# PX4FMUv1_7.net
KiCad netlist of a schematic drawn in EAGLE
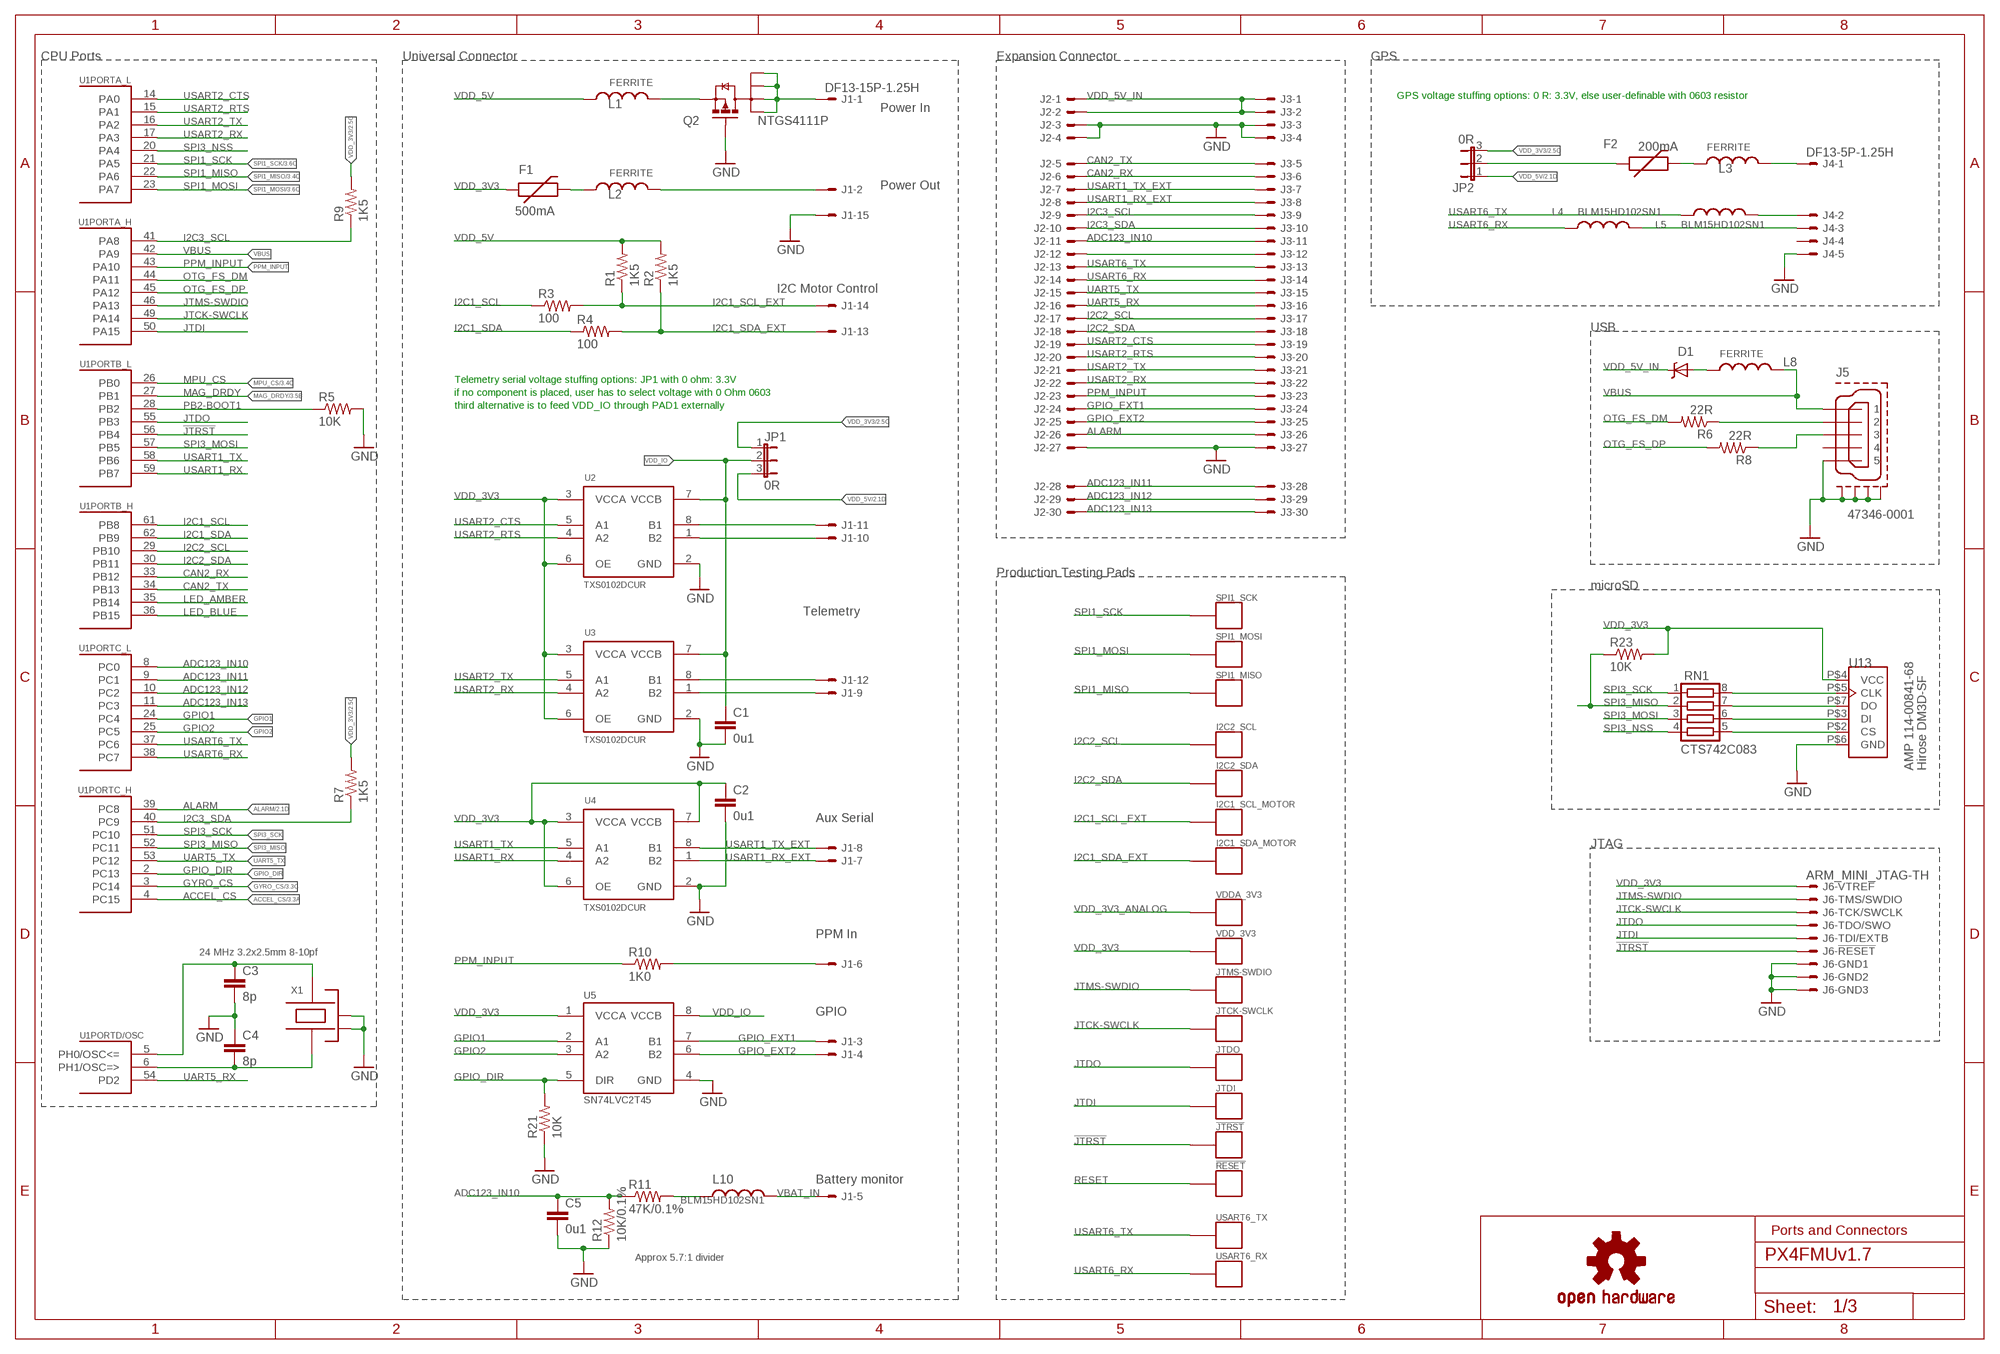
[diagram p0: schematic, sheet 1]
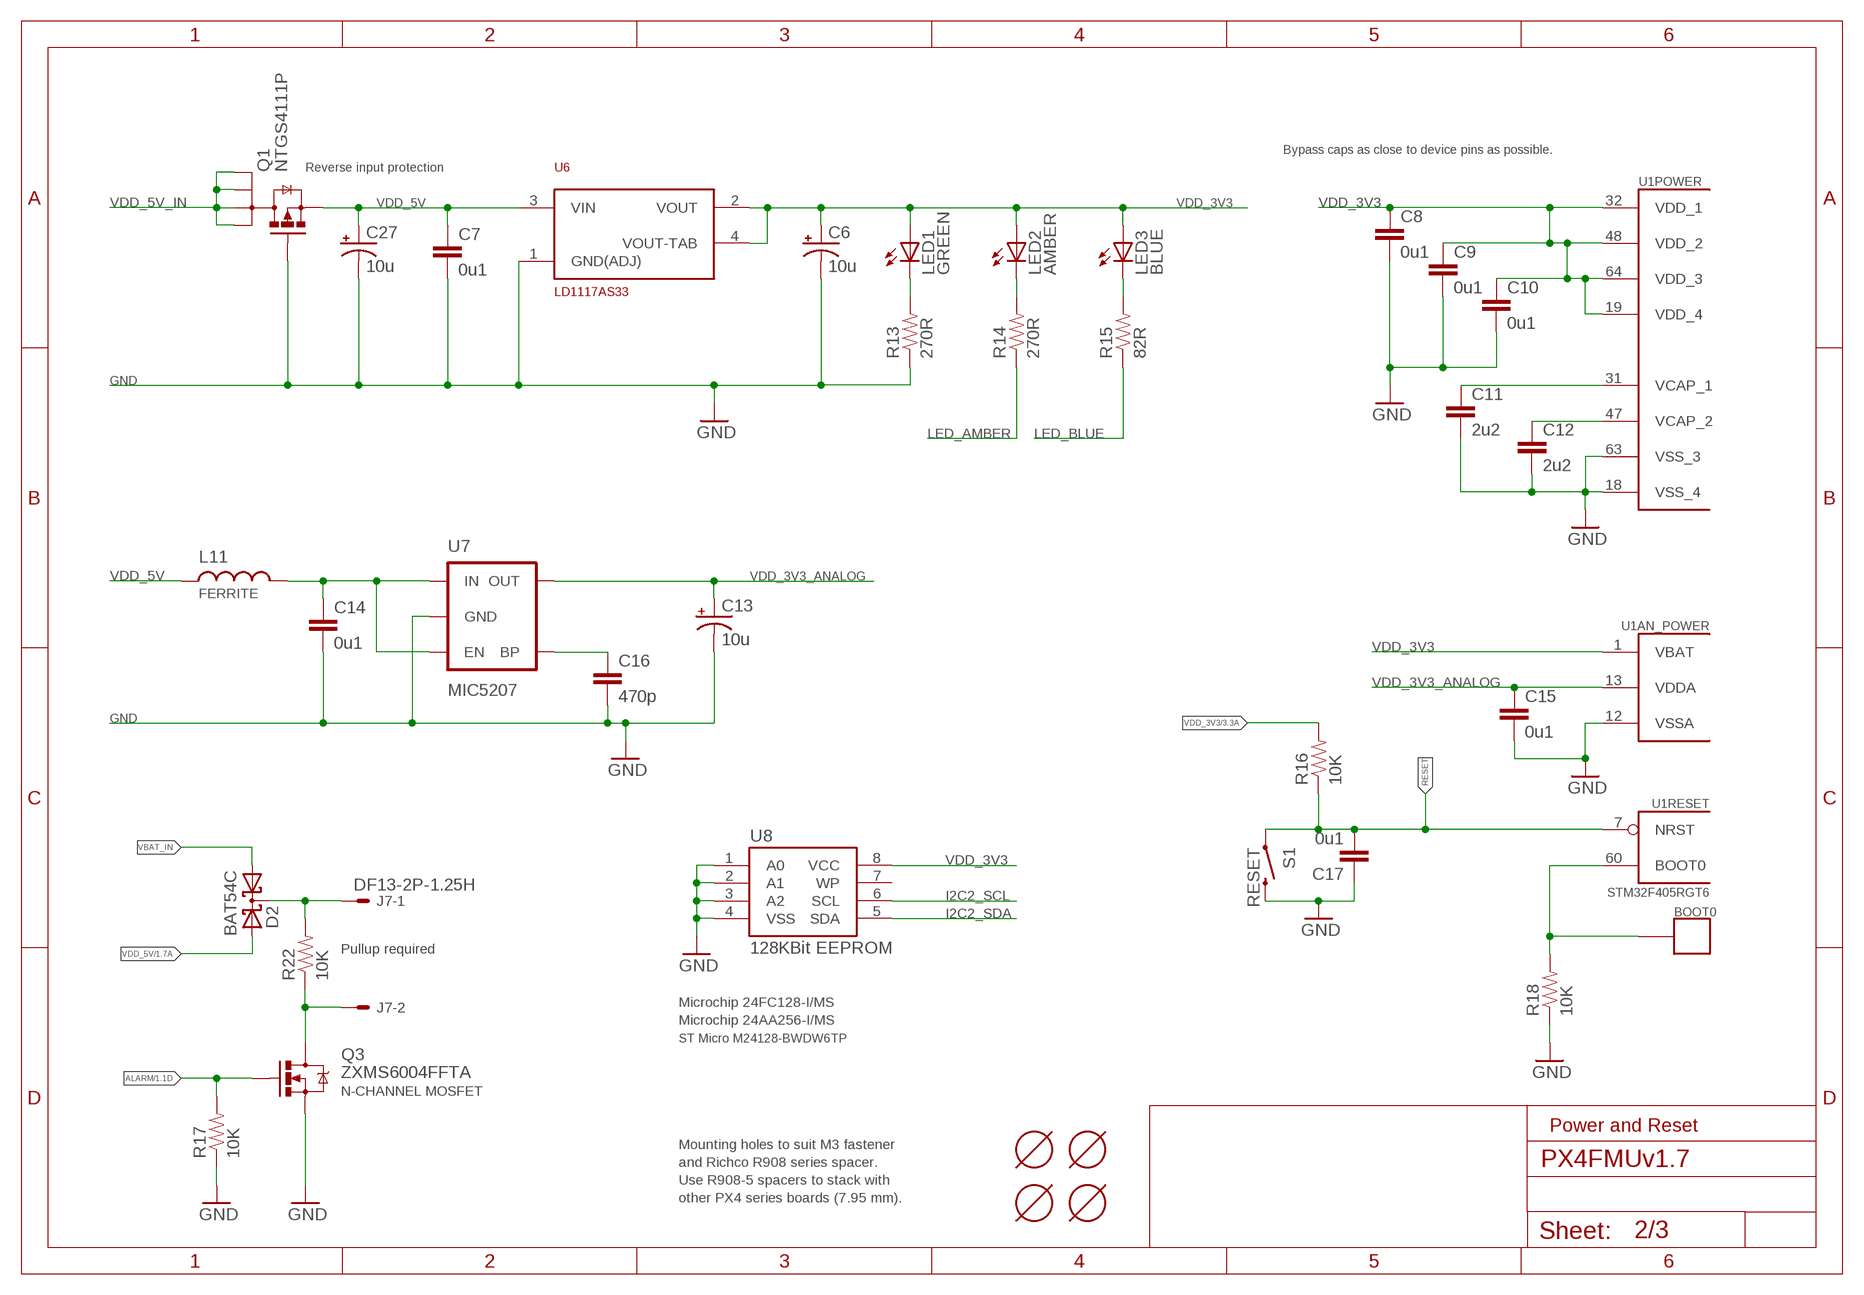
[diagram p1: schematic, sheet 2]
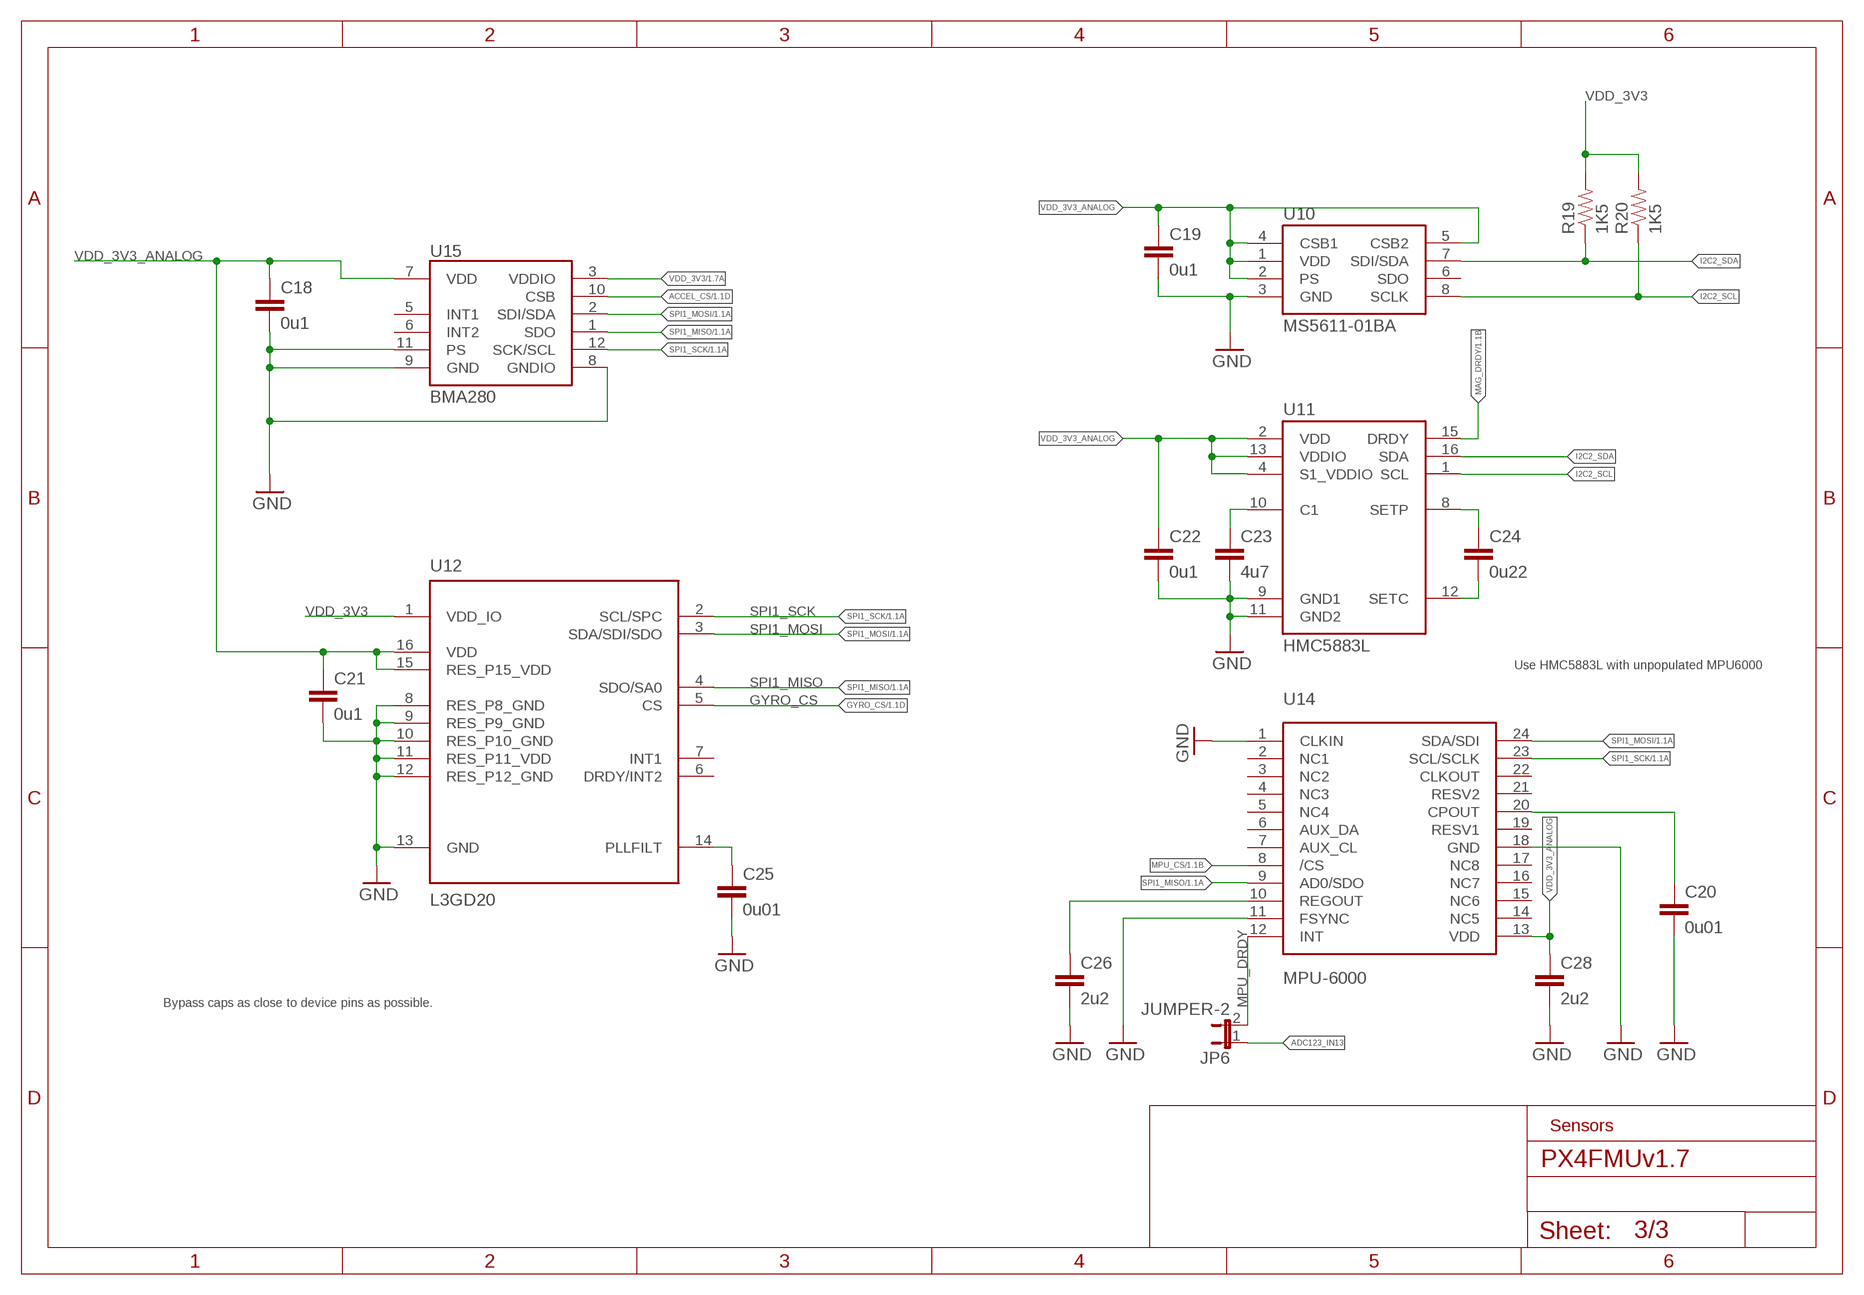
[diagram p2: schematic, sheet 3]

(export (version "E")
  (design (tool "Eeschema 10.0.6"))
  (components
    (comp (ref "C18")
      (value "0u1")
      (footprint "eagle-import:0402-CAP")
      (fields (field (name "PARTNO") "CC0402ZRY5V7BB104"))
      (libsource (lib "eagle-import") (part "CAP0402-CAP"))
    )
    (comp (ref "C19")
      (value "0u1")
      (footprint "eagle-import:0402-CAP")
      (fields (field (name "PARTNO") "CC0402ZRY5V7BB104"))
      (libsource (lib "eagle-import") (part "CAP0402-CAP"))
    )
    (comp (ref "C20")
      (value "0u01")
      (footprint "eagle-import:0402-CAP")
      (fields (field (name "PARTNO") "CC0402KRX7R7BB103"))
      (libsource (lib "eagle-import") (part "CAP0402-CAP"))
    )
    (comp (ref "C21")
      (value "0u1")
      (footprint "eagle-import:0402-CAP")
      (fields (field (name "PARTNO") "CC0402ZRY5V7BB104"))
      (libsource (lib "eagle-import") (part "CAP0402-CAP"))
    )
    (comp (ref "C22")
      (value "0u1")
      (footprint "eagle-import:0402-CAP")
      (fields (field (name "PARTNO") "CC0402ZRY5V7BB104"))
      (libsource (lib "eagle-import") (part "CAP0402-CAP"))
    )
    (comp (ref "C23")
      (value "4u7")
      (footprint "eagle-import:0402-CAP")
      (fields (field (name "PARTNO") "C1608Y5V0J475Z"))
      (libsource (lib "eagle-import") (part "CAP0402-CAP"))
    )
    (comp (ref "C24")
      (value "0u22")
      (footprint "eagle-import:0402-CAP")
      (fields (field (name "PARTNO") "C1005Y5V1C224Z"))
      (libsource (lib "eagle-import") (part "CAP0402-CAP"))
    )
    (comp (ref "C25")
      (value "0u01")
      (footprint "eagle-import:0402-CAP")
      (fields (field (name "PARTNO") "CC0402KRX7R7BB103"))
      (libsource (lib "eagle-import") (part "CAP0402-CAP"))
    )
    (comp (ref "C26")
      (value "2u2")
      (footprint "eagle-import:0402-CAP")
      (fields (field (name "PARTNO") "C1608Y5V1C225Z"))
      (libsource (lib "eagle-import") (part "CAP0402-CAP"))
    )
    (comp (ref "C28")
      (value "2u2")
      (footprint "eagle-import:0402-CAP")
      (fields (field (name "PARTNO") "C1608Y5V1C225Z"))
      (libsource (lib "eagle-import") (part "CAP0402-CAP"))
    )
    (comp (ref "JP6")
      (value "JUMPER-2")
      (footprint "eagle-import:SJ_2")
      (libsource (lib "eagle-import") (part "JUMPER-2"))
    )
    (comp (ref "R19")
      (value "1K5")
      (footprint "eagle-import:0402-RES")
      (fields (field (name "PARTNO") "RMCF0402JT1K50"))
      (libsource (lib "eagle-import") (part "RESISTOR0402-RES"))
    )
    (comp (ref "R20")
      (value "1K5")
      (footprint "eagle-import:0402-RES")
      (fields (field (name "PARTNO") "RMCF0402JT1K50"))
      (libsource (lib "eagle-import") (part "RESISTOR0402-RES"))
    )
    (comp (ref "U10")
      (value "MS5611-01BA")
      (footprint "eagle-import:MS5611-01BA")
      (libsource (lib "eagle-import") (part "MS5611-01BA"))
    )
    (comp (ref "U11")
      (value "HMC5883L")
      (footprint "eagle-import:HMC5883L-MAN")
      (libsource (lib "eagle-import") (part "HMC5883L"))
    )
    (comp (ref "U12")
      (value "L3GD20")
      (footprint "eagle-import:L3G4200DH-MAN")
      (libsource (lib "eagle-import") (part "L3G4200DH-LL"))
    )
    (comp (ref "U14")
      (value "MPU-6000")
      (footprint "eagle-import:QFN-24")
      (libsource (lib "eagle-import") (part "MPU-6000"))
    )
    (comp (ref "U15")
      (value "BMA280")
      (footprint "eagle-import:BMA280")
      (libsource (lib "eagle-import") (part "BMA280"))
    )
    (comp (ref "!JTRST")
      (value "PAD.04")
      (footprint "eagle-import:PAD.04X.04")
      (libsource (lib "eagle-import") (part "PAD.04"))
    )
    (comp (ref "!RESET")
      (value "PAD.04")
      (footprint "eagle-import:PAD.04X.04")
      (libsource (lib "eagle-import") (part "PAD.04"))
    )
    (comp (ref "C1")
      (value "0u1")
      (footprint "eagle-import:0402-CAP")
      (fields (field (name "PARTNO") "CC0402ZRY5V7BB104"))
      (libsource (lib "eagle-import") (part "CAP0402-CAP"))
    )
    (comp (ref "C2")
      (value "0u1")
      (footprint "eagle-import:0402-CAP")
      (fields (field (name "PARTNO") "CC0402ZRY5V7BB104"))
      (libsource (lib "eagle-import") (part "CAP0402-CAP"))
    )
    (comp (ref "C3")
      (value "8p")
      (footprint "eagle-import:0402-CAP")
      (fields (field (name "PARTNO") "C1005C0G1H080C"))
      (libsource (lib "eagle-import") (part "CAP0402-CAP"))
    )
    (comp (ref "C4")
      (value "8p")
      (footprint "eagle-import:0402-CAP")
      (fields (field (name "PARTNO") "C1005C0G1H080C"))
      (libsource (lib "eagle-import") (part "CAP0402-CAP"))
    )
    (comp (ref "C5")
      (value "0u1")
      (footprint "eagle-import:0402-CAP")
      (fields (field (name "PARTNO") "CC0402ZRY5V7BB104"))
      (libsource (lib "eagle-import") (part "CAP0402-CAP"))
    )
    (comp (ref "D1")
      (value "MSS1P4-M3")
      (footprint "eagle-import:MICROSMP")
      (fields (field (name "PARTNO") "MSS1P4-M3/89A"))
      (libsource (lib "eagle-import") (part "DIODE-SCHOTTKY_MSMP"))
    )
    (comp (ref "F1")
      (value "500mA")
      (footprint "eagle-import:0402-PTC")
      (fields (field (name "PARTNO") "MF-FSMF050X-2"))
      (libsource (lib "eagle-import") (part "PTC0402"))
    )
    (comp (ref "F2")
      (value "200mA")
      (footprint "eagle-import:0402-PTC")
      (fields (field (name "PARTNO") "MF-FSMF020X-2"))
      (libsource (lib "eagle-import") (part "PTC0402"))
    )
    (comp (ref "I2C1_SCL_MOTOR")
      (value "PAD.03")
      (footprint "eagle-import:PAD.03X.03")
      (libsource (lib "eagle-import") (part "PAD.03"))
    )
    (comp (ref "I2C1_SDA_MOTOR")
      (value "PAD.03")
      (footprint "eagle-import:PAD.03X.03")
      (libsource (lib "eagle-import") (part "PAD.03"))
    )
    (comp (ref "I2C2_SCL")
      (value "PAD.03")
      (footprint "eagle-import:PAD.03X.03")
      (libsource (lib "eagle-import") (part "PAD.03"))
    )
    (comp (ref "I2C2_SDA")
      (value "PAD.04")
      (footprint "eagle-import:PAD.04X.04")
      (libsource (lib "eagle-import") (part "PAD.04"))
    )
    (comp (ref "J1")
      (value "DF13-15P-1.25H")
      (footprint "eagle-import:DF13A-15P-1.25H")
      (fields (field (name "PARTNO") "DF13A-15P-1.25H(20)"))
      (libsource (lib "eagle-import") (part "DF13-15P-1.25?H"))
    )
    (comp (ref "J2")
      (value "HEADER_2X15-REV")
      (footprint "eagle-import:HEADER_2MM_2X15_REVERSE")
      (fields (field (name "BOM") "EXCLUDE") (field (name "PARTNO") "953230-2000-AR-PR"))
      (libsource (lib "eagle-import") (part "HEADER_2X15-REV"))
    )
    (comp (ref "J3")
      (value "HEADER_2X15")
      (footprint "eagle-import:HEADER_2MM_2X15")
      (fields (field (name "PARTNO") "953230-2000-AR-PR"))
      (libsource (lib "eagle-import") (part "HEADER_2X15-SMD"))
    )
    (comp (ref "J4")
      (value "DF13-5P-1.25H")
      (footprint "eagle-import:DF13A-5P-1.25H")
      (fields (field (name "PARTNO") "DF13A-5P-1.25H(20)"))
      (libsource (lib "eagle-import") (part "DF13-5P-1.25?H"))
    )
    (comp (ref "J5")
      (value "47346-0001")
      (footprint "eagle-import:MOLEX-47346-0001")
      (libsource (lib "eagle-import") (part "MOLEX-47346-0001"))
    )
    (comp (ref "J6")
      (value "ARM_MINI_JTAG-TH")
      (footprint "eagle-import:FTSH-105-01-XXX-DV")
      (fields (field (name "PARTNO") "M50-3900542"))
      (libsource (lib "eagle-import") (part "ARM_MINI_JTAG-TH"))
    )
    (comp (ref "JP1")
      (value "0R")
      (footprint "eagle-import:SJ_3_0603_PASTE1&2")
      (fields (field (name "PARTNO") "RMCF0402ZT0R00"))
      (libsource (lib "eagle-import") (part "JUMPER-30603"))
    )
    (comp (ref "JP2")
      (value "0R")
      (footprint "eagle-import:SJ_3_0603_PASTE1&2")
      (fields (field (name "PARTNO") "RMCF0402ZT0R00"))
      (libsource (lib "eagle-import") (part "JUMPER-30603"))
    )
    (comp (ref "JTCK-SWCLK")
      (value "PAD.04")
      (footprint "eagle-import:PAD.04X.04")
      (libsource (lib "eagle-import") (part "PAD.04"))
    )
    (comp (ref "JTDI")
      (value "PAD.04")
      (footprint "eagle-import:PAD.04X.04")
      (libsource (lib "eagle-import") (part "PAD.04"))
    )
    (comp (ref "JTDO")
      (value "PAD.04")
      (footprint "eagle-import:PAD.04X.04")
      (libsource (lib "eagle-import") (part "PAD.04"))
    )
    (comp (ref "JTMS-SWDIO")
      (value "PAD.04")
      (footprint "eagle-import:PAD.04X.04")
      (libsource (lib "eagle-import") (part "PAD.04"))
    )
    (comp (ref "L1")
      (value "FERRITE")
      (footprint "eagle-import:0402-IND")
      (fields (field (name "PARTNO") "BKP1005HS121-T"))
      (libsource (lib "eagle-import") (part "INDUCTOR0402"))
    )
    (comp (ref "L2")
      (value "FERRITE")
      (footprint "eagle-import:0402-IND")
      (fields (field (name "PARTNO") "BKP1005HS121-T"))
      (libsource (lib "eagle-import") (part "INDUCTOR0402"))
    )
    (comp (ref "L3")
      (value "FERRITE")
      (footprint "eagle-import:0402-IND")
      (fields (field (name "PARTNO") "BKP1005HS121-T"))
      (libsource (lib "eagle-import") (part "INDUCTOR0402"))
    )
    (comp (ref "L4")
      (value "BLM15HD102SN1")
      (footprint "eagle-import:0402-IND")
      (libsource (lib "eagle-import") (part "INDUCTOR0402"))
    )
    (comp (ref "L5")
      (value "BLM15HD102SN1")
      (footprint "eagle-import:0402-IND")
      (libsource (lib "eagle-import") (part "INDUCTOR0402"))
    )
    (comp (ref "L8")
      (value "FERRITE")
      (footprint "eagle-import:0402-IND")
      (fields (field (name "PARTNO") "BKP1005HS121-T"))
      (libsource (lib "eagle-import") (part "INDUCTOR0402"))
    )
    (comp (ref "L10")
      (value "BLM15HD102SN1")
      (footprint "eagle-import:0402-IND")
      (libsource (lib "eagle-import") (part "INDUCTOR0402"))
    )
    (comp (ref "Q2")
      (value "NTGS4111P")
      (footprint "eagle-import:TSOP-6")
      (libsource (lib "eagle-import") (part "NTGS4111P"))
    )
    (comp (ref "R1")
      (value "1K5")
      (footprint "eagle-import:0402-RES")
      (fields (field (name "PARTNO") "RMCF0402JT1K50"))
      (libsource (lib "eagle-import") (part "RESISTOR0402-RES"))
    )
    (comp (ref "R2")
      (value "1K5")
      (footprint "eagle-import:0402-RES")
      (fields (field (name "PARTNO") "RMCF0402JT1K50"))
      (libsource (lib "eagle-import") (part "RESISTOR0402-RES"))
    )
    (comp (ref "R3")
      (value "100")
      (footprint "eagle-import:0402-RES")
      (fields (field (name "PARTNO") "RMCF0402JT100R"))
      (libsource (lib "eagle-import") (part "RESISTOR0402-RES"))
    )
    (comp (ref "R4")
      (value "100")
      (footprint "eagle-import:0402-RES")
      (fields (field (name "PARTNO") "RMCF0402JT100R"))
      (libsource (lib "eagle-import") (part "RESISTOR0402-RES"))
    )
    (comp (ref "R5")
      (value "10K")
      (footprint "eagle-import:0402-RES")
      (fields (field (name "PARTNO") "RMCF0402FT10K0"))
      (libsource (lib "eagle-import") (part "RESISTOR0402-RES"))
    )
    (comp (ref "R6")
      (value "22R")
      (footprint "eagle-import:0402-RES")
      (fields (field (name "PARTNO") "RMCF0402JT22R0"))
      (libsource (lib "eagle-import") (part "RESISTOR0402-RES"))
    )
    (comp (ref "R7")
      (value "1K5")
      (footprint "eagle-import:0402-RES")
      (fields (field (name "PARTNO") "RMCF0402JT1K50"))
      (libsource (lib "eagle-import") (part "RESISTOR0402-RES"))
    )
    (comp (ref "R8")
      (value "22R")
      (footprint "eagle-import:0402-RES")
      (fields (field (name "PARTNO") "RMCF0402JT22R0"))
      (libsource (lib "eagle-import") (part "RESISTOR0402-RES"))
    )
    (comp (ref "R9")
      (value "1K5")
      (footprint "eagle-import:0402-RES")
      (fields (field (name "PARTNO") "RMCF0402JT1K50"))
      (libsource (lib "eagle-import") (part "RESISTOR0402-RES"))
    )
    (comp (ref "R10")
      (value "1K0")
      (footprint "eagle-import:0402-RES")
      (fields (field (name "PARTNO") "RMCF0402JT1K00"))
      (libsource (lib "eagle-import") (part "RESISTOR0402-RES"))
    )
    (comp (ref "R11")
      (value "47K/0.1%")
      (footprint "eagle-import:0402-RES")
      (fields (field (name "PARTNO") "ERA-2AEB473X"))
      (libsource (lib "eagle-import") (part "RESISTOR0402-RES"))
    )
    (comp (ref "R12")
      (value "10K/0.1%")
      (footprint "eagle-import:0402-RES")
      (fields (field (name "PARTNO") "ERA-2AEB103X"))
      (libsource (lib "eagle-import") (part "RESISTOR0402-RES"))
    )
    (comp (ref "R21")
      (value "10K")
      (footprint "eagle-import:0402-RES")
      (fields (field (name "PARTNO") "RMCF0402FT10K0"))
      (libsource (lib "eagle-import") (part "RESISTOR0402-RES"))
    )
    (comp (ref "R23")
      (value "10K")
      (footprint "eagle-import:0402-RES")
      (fields (field (name "PARTNO") "RMCF0402FT10K0"))
      (libsource (lib "eagle-import") (part "RESISTOR0402-RES"))
    )
    (comp (ref "RN1")
      (value "CTS742C083")
      (footprint "eagle-import:CTS742C083")
      (fields (field (name "PARTNO") "TC164-JR-07100RL"))
      (libsource (lib "eagle-import") (part "CTS742C083"))
    )
    (comp (ref "SPI1_MISO")
      (value "PAD.04")
      (footprint "eagle-import:PAD.04X.04")
      (libsource (lib "eagle-import") (part "PAD.04"))
    )
    (comp (ref "SPI1_MOSI")
      (value "PAD.04")
      (footprint "eagle-import:PAD.04X.04")
      (libsource (lib "eagle-import") (part "PAD.04"))
    )
    (comp (ref "SPI1_SCK")
      (value "PAD.04")
      (footprint "eagle-import:PAD.04X.04")
      (libsource (lib "eagle-import") (part "PAD.04"))
    )
    (comp (ref "U$7")
      (value "OSHW-LOGOS")
      (footprint "eagle-import:OSHW-LOGO-S")
      (libsource (lib "eagle-import") (part "OSHW-LOGOS"))
    )
    (comp (ref "U1")
      (value "STM32F405RGT6")
      (footprint "eagle-import:TQFP64")
      (fields (field (name "PARTNO") "STM32F405RGT6"))
      (libsource (lib "eagle-import") (part "STM32F20X_TQFP64"))
    )
    (comp (ref "U2")
      (value "TXS0102DCUR")
      (footprint "eagle-import:TI-DCU")
      (libsource (lib "eagle-import") (part "TXS0102DCUR"))
    )
    (comp (ref "U3")
      (value "TXS0102DCUR")
      (footprint "eagle-import:TI-DCU")
      (libsource (lib "eagle-import") (part "TXS0102DCUR"))
    )
    (comp (ref "U4")
      (value "TXS0102DCUR")
      (footprint "eagle-import:TI-DCU")
      (libsource (lib "eagle-import") (part "TXS0102DCUR"))
    )
    (comp (ref "U5")
      (value "SN74LVC2T45")
      (footprint "eagle-import:TI-DCU")
      (libsource (lib "eagle-import") (part "SN74LVC2T45DCUR"))
    )
    (comp (ref "U13")
      (value "AMP 114-00841-68")
      (footprint "eagle-import:AMPHENOL_114-00841-68")
      (fields (field (name "PARTNO") "114-00841-68"))
      (libsource (lib "eagle-import") (part "SF-MICROSDAMP-114-00841-68"))
    )
    (comp (ref "USART6_RX")
      (value "PAD.04")
      (footprint "eagle-import:PAD.04X.04")
      (libsource (lib "eagle-import") (part "PAD.04"))
    )
    (comp (ref "USART6_TX")
      (value "PAD.04")
      (footprint "eagle-import:PAD.04X.04")
      (libsource (lib "eagle-import") (part "PAD.04"))
    )
    (comp (ref "VDDA_3V3")
      (value "PAD.04")
      (footprint "eagle-import:PAD.04X.04")
      (libsource (lib "eagle-import") (part "PAD.04"))
    )
    (comp (ref "VDD_3V3")
      (value "PAD.04")
      (footprint "eagle-import:PAD.04X.04")
      (libsource (lib "eagle-import") (part "PAD.04"))
    )
    (comp (ref "X1")
      (value "24 MHz 3.2x2.5mm 8-10pf")
      (footprint "eagle-import:OSCILLATOR-3.2X2.5")
      (fields (field (name "PARTNO") "NX3225SA-24.000000MHZ"))
      (libsource (lib "eagle-import") (part "OSCILLATOR-3.2X2.5"))
    )
    (comp (ref "BOOT0")
      (value "PAD.04")
      (footprint "eagle-import:PAD.04X.04")
      (libsource (lib "eagle-import") (part "PAD.04"))
    )
    (comp (ref "C6")
      (value "10u")
      (footprint "eagle-import:EIA3216")
      (fields (field (name "PARTNO") "F931A106MAA"))
      (libsource (lib "eagle-import") (part "CAP_POL1206"))
    )
    (comp (ref "C7")
      (value "0u1")
      (footprint "eagle-import:0402-CAP")
      (fields (field (name "PARTNO") "CC0402ZRY5V7BB104"))
      (libsource (lib "eagle-import") (part "CAP0402-CAP"))
    )
    (comp (ref "C8")
      (value "0u1")
      (footprint "eagle-import:0402-CAP")
      (fields (field (name "PARTNO") "CC0402ZRY5V7BB104"))
      (libsource (lib "eagle-import") (part "CAP0402-CAP"))
    )
    (comp (ref "C9")
      (value "0u1")
      (footprint "eagle-import:0402-CAP")
      (fields (field (name "PARTNO") "CC0402ZRY5V7BB104"))
      (libsource (lib "eagle-import") (part "CAP0402-CAP"))
    )
    (comp (ref "C10")
      (value "0u1")
      (footprint "eagle-import:0402-CAP")
      (fields (field (name "PARTNO") "CC0402ZRY5V7BB104"))
      (libsource (lib "eagle-import") (part "CAP0402-CAP"))
    )
    (comp (ref "C11")
      (value "2u2")
      (footprint "eagle-import:0402-CAP")
      (fields (field (name "PARTNO") "C1608Y5V1C225Z"))
      (libsource (lib "eagle-import") (part "CAP0402-CAP"))
    )
    (comp (ref "C12")
      (value "2u2")
      (footprint "eagle-import:0402-CAP")
      (fields (field (name "PARTNO") "C1608Y5V1C225Z"))
      (libsource (lib "eagle-import") (part "CAP0402-CAP"))
    )
    (comp (ref "C13")
      (value "10u")
      (footprint "eagle-import:EIA3216")
      (fields (field (name "PARTNO") "F931A106MAA"))
      (libsource (lib "eagle-import") (part "CAP_POL1206"))
    )
    (comp (ref "C14")
      (value "0u1")
      (footprint "eagle-import:0402-CAP")
      (fields (field (name "PARTNO") "CC0402ZRY5V7BB104"))
      (libsource (lib "eagle-import") (part "CAP0402-CAP"))
    )
    (comp (ref "C15")
      (value "0u1")
      (footprint "eagle-import:0402-CAP")
      (fields (field (name "PARTNO") "CC0402ZRY5V7BB104"))
      (libsource (lib "eagle-import") (part "CAP0402-CAP"))
    )
    (comp (ref "C16")
      (value "470p")
      (footprint "eagle-import:0402-CAP")
      (fields (field (name "PARTNO") "CC0402KRX7R9BB471"))
      (libsource (lib "eagle-import") (part "CAP0402-CAP"))
    )
    (comp (ref "C17")
      (value "0u1")
      (footprint "eagle-import:0402-CAP")
      (fields (field (name "PARTNO") "CC0402ZRY5V7BB104"))
      (libsource (lib "eagle-import") (part "CAP0402-CAP"))
    )
    (comp (ref "C27")
      (value "10u")
      (footprint "eagle-import:EIA3216")
      (fields (field (name "PARTNO") "F931A106MAA"))
      (libsource (lib "eagle-import") (part "CAP_POL1206"))
    )
    (comp (ref "D2")
      (value "BAT54C")
      (footprint "eagle-import:SOT23-3")
      (fields (field (name "PARTNO") "BAT54C-7-F"))
      (libsource (lib "eagle-import") (part "BAT54C"))
    )
    (comp (ref "J7")
      (value "DF13-2P-1.25H")
      (footprint "eagle-import:DF13A-2P-1.25H")
      (fields (field (name "PARTNO") "DF13-2P-1.25H(20)"))
      (libsource (lib "eagle-import") (part "DF13-2P-1.25?H"))
    )
    (comp (ref "L11")
      (value "FERRITE")
      (footprint "eagle-import:0402-IND")
      (fields (field (name "PARTNO") "BKP1005HS121-T"))
      (libsource (lib "eagle-import") (part "INDUCTOR0402"))
    )
    (comp (ref "LED1")
      (value "GREEN")
      (footprint "eagle-import:LED-0603")
      (fields (field (name "PARTNO") "LNJ337W83RA"))
      (libsource (lib "eagle-import") (part "LED0603"))
    )
    (comp (ref "LED2")
      (value "AMBER")
      (footprint "eagle-import:LED-0603")
      (fields (field (name "PARTNO") "LNJ437W84RA"))
      (libsource (lib "eagle-import") (part "LED0603"))
    )
    (comp (ref "LED3")
      (value "BLUE")
      (footprint "eagle-import:LED-0603")
      (fields (field (name "PARTNO") "LNJ937W8CRA"))
      (libsource (lib "eagle-import") (part "LED0603"))
    )
    (comp (ref "Q1")
      (value "NTGS4111P")
      (footprint "eagle-import:TSOP-6")
      (libsource (lib "eagle-import") (part "NTGS4111P"))
    )
    (comp (ref "Q3")
      (value "ZXMS6004FFTA")
      (footprint "eagle-import:SOT23-3")
      (libsource (lib "eagle-import") (part "MOSFET-NCHANNELSMD"))
    )
    (comp (ref "R13")
      (value "270R")
      (footprint "eagle-import:0402-RES")
      (fields (field (name "PARTNO") "RC0402JR-07270RL"))
      (libsource (lib "eagle-import") (part "RESISTOR0402-RES"))
    )
    (comp (ref "R14")
      (value "270R")
      (footprint "eagle-import:0402-RES")
      (fields (field (name "PARTNO") "RC0402JR-07270RL"))
      (libsource (lib "eagle-import") (part "RESISTOR0402-RES"))
    )
    (comp (ref "R15")
      (value "82R")
      (footprint "eagle-import:0402-RES")
      (fields (field (name "PARTNO") "RC0402JR-0782RL"))
      (libsource (lib "eagle-import") (part "RESISTOR0402-RES"))
    )
    (comp (ref "R16")
      (value "10K")
      (footprint "eagle-import:0402-RES")
      (fields (field (name "PARTNO") "RMCF0402FT10K0"))
      (libsource (lib "eagle-import") (part "RESISTOR0402-RES"))
    )
    (comp (ref "R17")
      (value "10K")
      (footprint "eagle-import:0402-RES")
      (fields (field (name "PARTNO") "RMCF0402FT10K0"))
      (libsource (lib "eagle-import") (part "RESISTOR0402-RES"))
    )
    (comp (ref "R18")
      (value "10K")
      (footprint "eagle-import:0402-RES")
      (fields (field (name "PARTNO") "RMCF0402FT10K0"))
      (libsource (lib "eagle-import") (part "RESISTOR0402-RES"))
    )
    (comp (ref "R22")
      (value "10K")
      (footprint "eagle-import:0402-RES")
      (fields (field (name "PARTNO") "RMCF0402FT10K0"))
      (libsource (lib "eagle-import") (part "RESISTOR0402-RES"))
    )
    (comp (ref "S1")
      (value "RESET")
      (footprint "eagle-import:EVQP7J01K")
      (fields (field (name "PARTNO") "EVQP7J01K"))
      (libsource (lib "eagle-import") (part "SWITCH-MOMENTARY-2"))
    )
    (comp (ref "U$1")
      (value "MOUNT-HOLE3.1MM")
      (footprint "eagle-import:MOUNT-HOLE3.1")
      (libsource (lib "eagle-import") (part "MOUNT-HOLE3.1MM"))
    )
    (comp (ref "U$2")
      (value "MOUNT-HOLE3.1MM")
      (footprint "eagle-import:MOUNT-HOLE3.1")
      (libsource (lib "eagle-import") (part "MOUNT-HOLE3.1MM"))
    )
    (comp (ref "U$3")
      (value "MOUNT-HOLE3.1MM")
      (footprint "eagle-import:MOUNT-HOLE3.1")
      (libsource (lib "eagle-import") (part "MOUNT-HOLE3.1MM"))
    )
    (comp (ref "U$4")
      (value "MOUNT-HOLE3.1MM")
      (footprint "eagle-import:MOUNT-HOLE3.1")
      (libsource (lib "eagle-import") (part "MOUNT-HOLE3.1MM"))
    )
    (comp (ref "U6")
      (value "LD1117AS33")
      (footprint "eagle-import:SOT-223")
      (libsource (lib "eagle-import") (part "LD1117AS33"))
    )
    (comp (ref "U7")
      (value "MIC5207")
      (footprint "eagle-import:SOT23-5")
      (fields (field (name "PARTNO") "MIC5207-3.3YM5"))
      (libsource (lib "eagle-import") (part "V_REG_LDOSMD"))
    )
    (comp (ref "U8")
      (value "128KBit EEPROM")
      (footprint "eagle-import:MSOP-8")
      (fields (field (name "PARTNO") "24FC128-I/MS"))
      (libsource (lib "eagle-import") (part "EEPROM-I2CMSOP"))
    )
  )
  (nets
    (net (code "1") (name "ACCEL_CS") (class "Default")
      (node (ref "U1") (pin "4") (pinfunction "PC15_4") (pintype "bidirectional"))
      (node (ref "U15") (pin "10") (pinfunction "CSB_10") (pintype "bidirectional"))
    )
    (net (code "2") (name "ADC123_IN10") (class "Default")
      (node (ref "C5") (pin "1") (pinfunction "1_1") (pintype "passive"))
      (node (ref "J2") (pin "11") (pinfunction "S_11") (pintype "passive"))
      (node (ref "J3") (pin "11") (pinfunction "S_11") (pintype "passive"))
      (node (ref "R11") (pin "1") (pinfunction "1_1") (pintype "passive"))
      (node (ref "R12") (pin "2") (pinfunction "2_2") (pintype "passive"))
      (node (ref "U1") (pin "8") (pinfunction "PC0_8") (pintype "bidirectional"))
    )
    (net (code "3") (name "ADC123_IN11") (class "Default")
      (node (ref "J2") (pin "28") (pinfunction "S_28") (pintype "passive"))
      (node (ref "J3") (pin "28") (pinfunction "S_28") (pintype "passive"))
      (node (ref "U1") (pin "9") (pinfunction "PC1_9") (pintype "bidirectional"))
    )
    (net (code "4") (name "ADC123_IN12") (class "Default")
      (node (ref "J2") (pin "29") (pinfunction "S_29") (pintype "passive"))
      (node (ref "J3") (pin "29") (pinfunction "S_29") (pintype "passive"))
      (node (ref "U1") (pin "10") (pinfunction "PC2_10") (pintype "bidirectional"))
    )
    (net (code "5") (name "ADC123_IN13") (class "Default")
      (node (ref "J2") (pin "30") (pinfunction "S_30") (pintype "passive"))
      (node (ref "J3") (pin "30") (pinfunction "S_30") (pintype "passive"))
      (node (ref "JP6") (pin "1") (pinfunction "1_1") (pintype "passive"))
      (node (ref "U1") (pin "11") (pinfunction "PC3_11") (pintype "bidirectional"))
    )
    (net (code "6") (name "ALARM") (class "Default")
      (node (ref "J2") (pin "26") (pinfunction "S_26") (pintype "passive"))
      (node (ref "J3") (pin "26") (pinfunction "S_26") (pintype "passive"))
      (node (ref "Q3") (pin "1") (pinfunction "G_1") (pintype "passive"))
      (node (ref "R17") (pin "2") (pinfunction "2_2") (pintype "passive"))
      (node (ref "U1") (pin "39") (pinfunction "PC8_39") (pintype "bidirectional"))
    )
    (net (code "7") (name "CAN2_RX") (class "Default")
      (node (ref "J2") (pin "6") (pinfunction "S_6") (pintype "passive"))
      (node (ref "J3") (pin "6") (pinfunction "S_6") (pintype "passive"))
      (node (ref "U1") (pin "33") (pinfunction "PB12_33") (pintype "bidirectional"))
    )
    (net (code "8") (name "CAN2_TX") (class "Default")
      (node (ref "J2") (pin "5") (pinfunction "S_5") (pintype "passive"))
      (node (ref "J3") (pin "5") (pinfunction "S_5") (pintype "passive"))
      (node (ref "U1") (pin "34") (pinfunction "PB13_34") (pintype "bidirectional"))
    )
    (net (code "9") (name "GND") (class "Default")
      (node (ref "C1") (pin "2") (pinfunction "2_2") (pintype "passive"))
      (node (ref "C10") (pin "2") (pinfunction "2_2") (pintype "passive"))
      (node (ref "C11") (pin "2") (pinfunction "2_2") (pintype "passive"))
      (node (ref "C12") (pin "2") (pinfunction "2_2") (pintype "passive"))
      (node (ref "C13") (pin "C") (pinfunction "-_C") (pintype "passive"))
      (node (ref "C14") (pin "2") (pinfunction "2_2") (pintype "passive"))
      (node (ref "C15") (pin "2") (pinfunction "2_2") (pintype "passive"))
      (node (ref "C16") (pin "2") (pinfunction "2_2") (pintype "passive"))
      (node (ref "C17") (pin "1") (pinfunction "1_1") (pintype "passive"))
      (node (ref "C18") (pin "2") (pinfunction "2_2") (pintype "passive"))
      (node (ref "C19") (pin "2") (pinfunction "2_2") (pintype "passive"))
      (node (ref "C2") (pin "2") (pinfunction "2_2") (pintype "passive"))
      (node (ref "C20") (pin "2") (pinfunction "2_2") (pintype "passive"))
      (node (ref "C21") (pin "2") (pinfunction "2_2") (pintype "passive"))
      (node (ref "C22") (pin "2") (pinfunction "2_2") (pintype "passive"))
      (node (ref "C23") (pin "2") (pinfunction "2_2") (pintype "passive"))
      (node (ref "C25") (pin "2") (pinfunction "2_2") (pintype "passive"))
      (node (ref "C26") (pin "2") (pinfunction "2_2") (pintype "passive"))
      (node (ref "C27") (pin "C") (pinfunction "-_C") (pintype "passive"))
      (node (ref "C28") (pin "2") (pinfunction "2_2") (pintype "passive"))
      (node (ref "C3") (pin "2") (pinfunction "2_2") (pintype "passive"))
      (node (ref "C4") (pin "1") (pinfunction "1_1") (pintype "passive"))
      (node (ref "C5") (pin "2") (pinfunction "2_2") (pintype "passive"))
      (node (ref "C6") (pin "C") (pinfunction "-_C") (pintype "passive"))
      (node (ref "C7") (pin "2") (pinfunction "2_2") (pintype "passive"))
      (node (ref "C8") (pin "2") (pinfunction "2_2") (pintype "passive"))
      (node (ref "C9") (pin "2") (pinfunction "2_2") (pintype "passive"))
      (node (ref "J1") (pin "15") (pinfunction "S_15") (pintype "passive"))
      (node (ref "J2") (pin "27") (pinfunction "S_27") (pintype "passive"))
      (node (ref "J2") (pin "3") (pinfunction "S_3") (pintype "passive"))
      (node (ref "J2") (pin "4") (pinfunction "S_4") (pintype "passive"))
      (node (ref "J3") (pin "27") (pinfunction "S_27") (pintype "passive"))
      (node (ref "J3") (pin "3") (pinfunction "S_3") (pintype "passive"))
      (node (ref "J3") (pin "4") (pinfunction "S_4") (pintype "passive"))
      (node (ref "J4") (pin "5") (pinfunction "S_5") (pintype "passive"))
      (node (ref "J5") (pin "GND") (pinfunction "5_GND") (pintype "power_in"))
      (node (ref "J5") (pin "GND1") (pinfunction "GND1_GND1") (pintype "bidirectional"))
      (node (ref "J5") (pin "GND2") (pinfunction "GND2_GND2") (pintype "bidirectional"))
      (node (ref "J5") (pin "GND3") (pinfunction "GND3_GND3") (pintype "bidirectional"))
      (node (ref "J5") (pin "GND4") (pinfunction "GND4_GND4") (pintype "bidirectional"))
      (node (ref "J6") (pin "3") (pinfunction "S_3") (pintype "passive"))
      (node (ref "J6") (pin "5") (pinfunction "S_5") (pintype "passive"))
      (node (ref "J6") (pin "9") (pinfunction "S_9") (pintype "passive"))
      (node (ref "Q1") (pin "3") (pinfunction "G_3") (pintype "passive"))
      (node (ref "Q2") (pin "3") (pinfunction "G_3") (pintype "passive"))
      (node (ref "Q3") (pin "2") (pinfunction "S_2") (pintype "passive"))
      (node (ref "R12") (pin "1") (pinfunction "1_1") (pintype "passive"))
      (node (ref "R13") (pin "1") (pinfunction "1_1") (pintype "passive"))
      (node (ref "R17") (pin "1") (pinfunction "1_1") (pintype "passive"))
      (node (ref "R18") (pin "1") (pinfunction "1_1") (pintype "passive"))
      (node (ref "R21") (pin "1") (pinfunction "1_1") (pintype "passive"))
      (node (ref "R5") (pin "2") (pinfunction "2_2") (pintype "passive"))
      (node (ref "S1") (pin "B3") (pinfunction "2_B3") (pintype "passive"))
      (node (ref "U1") (pin "12") (pinfunction "VSSA_12") (pintype "power_in"))
      (node (ref "U1") (pin "18") (pinfunction "VSS_4_18") (pintype "power_in"))
      (node (ref "U1") (pin "63") (pinfunction "VSS_3_63") (pintype "power_in"))
      (node (ref "U10") (pin "3") (pinfunction "GND_3") (pintype "bidirectional"))
      (node (ref "U11") (pin "11") (pinfunction "GND2_11") (pintype "bidirectional"))
      (node (ref "U11") (pin "9") (pinfunction "GND1_9") (pintype "bidirectional"))
      (node (ref "U12") (pin "10") (pinfunction "RES_P10_GND_10") (pintype "bidirectional"))
      (node (ref "U12") (pin "11") (pinfunction "RES_P11_VDD_11") (pintype "bidirectional"))
      (node (ref "U12") (pin "12") (pinfunction "RES_P12_GND_12") (pintype "bidirectional"))
      (node (ref "U12") (pin "13") (pinfunction "GND_13") (pintype "bidirectional"))
      (node (ref "U12") (pin "8") (pinfunction "RES_P8_GND_8") (pintype "bidirectional"))
      (node (ref "U12") (pin "9") (pinfunction "RES_P9_GND_9") (pintype "bidirectional"))
      (node (ref "U13") (pin "P$6") (pinfunction "GND_P$6") (pintype "power_in"))
      (node (ref "U14") (pin "1") (pinfunction "CLKIN_1") (pintype "bidirectional"))
      (node (ref "U14") (pin "11") (pinfunction "FSYNC_11") (pintype "bidirectional"))
      (node (ref "U14") (pin "18") (pinfunction "GND_18") (pintype "bidirectional"))
      (node (ref "U15") (pin "11") (pinfunction "PS_11") (pintype "bidirectional"))
      (node (ref "U15") (pin "8") (pinfunction "GNDIO_8") (pintype "bidirectional"))
      (node (ref "U15") (pin "9") (pinfunction "GND_9") (pintype "bidirectional"))
      (node (ref "U2") (pin "2") (pinfunction "GND_2") (pintype "power_in"))
      (node (ref "U3") (pin "2") (pinfunction "GND_2") (pintype "power_in"))
      (node (ref "U4") (pin "2") (pinfunction "GND_2") (pintype "power_in"))
      (node (ref "U5") (pin "4") (pinfunction "GND_4") (pintype "power_in"))
      (node (ref "U6") (pin "1") (pinfunction "GND(ADJ)_1") (pintype "bidirectional"))
      (node (ref "U7") (pin "2") (pinfunction "GND_2") (pintype "input"))
      (node (ref "U8") (pin "1") (pinfunction "A0_1") (pintype "bidirectional"))
      (node (ref "U8") (pin "2") (pinfunction "A1_2") (pintype "bidirectional"))
      (node (ref "U8") (pin "3") (pinfunction "A2_3") (pintype "bidirectional"))
      (node (ref "U8") (pin "4") (pinfunction "VSS_4") (pintype "power_in"))
      (node (ref "X1") (pin "2") (pinfunction "NC_2_2") (pintype "power_in"))
      (node (ref "X1") (pin "4") (pinfunction "NC_4_4") (pintype "power_in"))
    )
    (net (code "10") (name "GPIO1") (class "Default")
      (node (ref "U1") (pin "24") (pinfunction "PC4_24") (pintype "bidirectional"))
      (node (ref "U5") (pin "2") (pinfunction "A1_2") (pintype "bidirectional"))
    )
    (net (code "11") (name "GPIO2") (class "Default")
      (node (ref "U1") (pin "25") (pinfunction "PC5_25") (pintype "bidirectional"))
      (node (ref "U5") (pin "3") (pinfunction "A2_3") (pintype "bidirectional"))
    )
    (net (code "12") (name "GPIO_DIR") (class "Default")
      (node (ref "R21") (pin "2") (pinfunction "2_2") (pintype "passive"))
      (node (ref "U1") (pin "2") (pinfunction "PC13_2") (pintype "bidirectional"))
      (node (ref "U5") (pin "5") (pinfunction "DIR_5") (pintype "input"))
    )
    (net (code "13") (name "GPIO_EXT1") (class "Default")
      (node (ref "J1") (pin "3") (pinfunction "S_3") (pintype "passive"))
      (node (ref "J2") (pin "24") (pinfunction "S_24") (pintype "passive"))
      (node (ref "J3") (pin "24") (pinfunction "S_24") (pintype "passive"))
      (node (ref "U5") (pin "7") (pinfunction "B1_7") (pintype "bidirectional"))
    )
    (net (code "14") (name "GPIO_EXT2") (class "Default")
      (node (ref "J1") (pin "4") (pinfunction "S_4") (pintype "passive"))
      (node (ref "J2") (pin "25") (pinfunction "S_25") (pintype "passive"))
      (node (ref "J3") (pin "25") (pinfunction "S_25") (pintype "passive"))
      (node (ref "U5") (pin "6") (pinfunction "B2_6") (pintype "bidirectional"))
    )
    (net (code "15") (name "GYRO_CS") (class "Default")
      (node (ref "U1") (pin "3") (pinfunction "PC14_3") (pintype "bidirectional"))
      (node (ref "U12") (pin "5") (pinfunction "CS_5") (pintype "input"))
    )
    (net (code "16") (name "I2C1_SCL") (class "Default")
      (node (ref "R3") (pin "1") (pinfunction "1_1") (pintype "passive"))
      (node (ref "U1") (pin "61") (pinfunction "PB8_61") (pintype "bidirectional"))
    )
    (net (code "17") (name "I2C1_SCL_EXT") (class "Default")
      (node (ref "I2C1_SCL_MOTOR") (pin "P$1") (pinfunction "P$1_P$1") (pintype "passive"))
      (node (ref "J1") (pin "14") (pinfunction "S_14") (pintype "passive"))
      (node (ref "R1") (pin "1") (pinfunction "1_1") (pintype "passive"))
      (node (ref "R3") (pin "2") (pinfunction "2_2") (pintype "passive"))
    )
    (net (code "18") (name "I2C1_SDA") (class "Default")
      (node (ref "R4") (pin "1") (pinfunction "1_1") (pintype "passive"))
      (node (ref "U1") (pin "62") (pinfunction "PB9_62") (pintype "bidirectional"))
    )
    (net (code "19") (name "I2C1_SDA_EXT") (class "Default")
      (node (ref "I2C1_SDA_MOTOR") (pin "P$1") (pinfunction "P$1_P$1") (pintype "passive"))
      (node (ref "J1") (pin "13") (pinfunction "S_13") (pintype "passive"))
      (node (ref "R2") (pin "1") (pinfunction "1_1") (pintype "passive"))
      (node (ref "R4") (pin "2") (pinfunction "2_2") (pintype "passive"))
    )
    (net (code "20") (name "I2C2_SCL") (class "Default")
      (node (ref "I2C2_SCL") (pin "P$1") (pinfunction "P$1_P$1") (pintype "passive"))
      (node (ref "J2") (pin "17") (pinfunction "S_17") (pintype "passive"))
      (node (ref "J3") (pin "17") (pinfunction "S_17") (pintype "passive"))
      (node (ref "R20") (pin "1") (pinfunction "1_1") (pintype "passive"))
      (node (ref "U1") (pin "29") (pinfunction "PB10_29") (pintype "bidirectional"))
      (node (ref "U10") (pin "8") (pinfunction "SCLK_8") (pintype "bidirectional"))
      (node (ref "U11") (pin "1") (pinfunction "SCL_1") (pintype "bidirectional"))
      (node (ref "U8") (pin "6") (pinfunction "SCL_6") (pintype "bidirectional"))
    )
    (net (code "21") (name "I2C2_SDA") (class "Default")
      (node (ref "I2C2_SDA") (pin "P$1") (pinfunction "P$1_P$1") (pintype "passive"))
      (node (ref "J2") (pin "18") (pinfunction "S_18") (pintype "passive"))
      (node (ref "J3") (pin "18") (pinfunction "S_18") (pintype "passive"))
      (node (ref "R19") (pin "1") (pinfunction "1_1") (pintype "passive"))
      (node (ref "U1") (pin "30") (pinfunction "PB11_30") (pintype "bidirectional"))
      (node (ref "U10") (pin "7") (pinfunction "SDI/SDA_7") (pintype "bidirectional"))
      (node (ref "U11") (pin "16") (pinfunction "SDA_16") (pintype "bidirectional"))
      (node (ref "U8") (pin "5") (pinfunction "SDA_5") (pintype "bidirectional"))
    )
    (net (code "22") (name "I2C3_SCL") (class "Default")
      (node (ref "J2") (pin "9") (pinfunction "S_9") (pintype "passive"))
      (node (ref "J3") (pin "9") (pinfunction "S_9") (pintype "passive"))
      (node (ref "R9") (pin "1") (pinfunction "1_1") (pintype "passive"))
      (node (ref "U1") (pin "41") (pinfunction "PA8_41") (pintype "bidirectional"))
    )
    (net (code "23") (name "I2C3_SDA") (class "Default")
      (node (ref "J2") (pin "10") (pinfunction "S_10") (pintype "passive"))
      (node (ref "J3") (pin "10") (pinfunction "S_10") (pintype "passive"))
      (node (ref "R7") (pin "1") (pinfunction "1_1") (pintype "passive"))
      (node (ref "U1") (pin "40") (pinfunction "PC9_40") (pintype "bidirectional"))
    )
    (net (code "24") (name "JTCK-SWCLK") (class "Default")
      (node (ref "J6") (pin "4") (pinfunction "S_4") (pintype "passive"))
      (node (ref "JTCK-SWCLK") (pin "P$1") (pinfunction "P$1_P$1") (pintype "passive"))
      (node (ref "U1") (pin "49") (pinfunction "PA14_49") (pintype "bidirectional"))
    )
    (net (code "25") (name "JTDI") (class "Default")
      (node (ref "J6") (pin "8") (pinfunction "S_8") (pintype "passive"))
      (node (ref "JTDI") (pin "P$1") (pinfunction "P$1_P$1") (pintype "passive"))
      (node (ref "U1") (pin "50") (pinfunction "PA15_50") (pintype "bidirectional"))
    )
    (net (code "26") (name "JTDO") (class "Default")
      (node (ref "J6") (pin "6") (pinfunction "S_6") (pintype "passive"))
      (node (ref "JTDO") (pin "P$1") (pinfunction "P$1_P$1") (pintype "passive"))
      (node (ref "U1") (pin "55") (pinfunction "PB3_55") (pintype "bidirectional"))
    )
    (net (code "27") (name "JTMS-SWDIO") (class "Default")
      (node (ref "J6") (pin "2") (pinfunction "S_2") (pintype "passive"))
      (node (ref "JTMS-SWDIO") (pin "P$1") (pinfunction "P$1_P$1") (pintype "passive"))
      (node (ref "U1") (pin "46") (pinfunction "PA13_46") (pintype "bidirectional"))
    )
    (net (code "28") (name "LED_AMBER") (class "Default")
      (node (ref "R14") (pin "1") (pinfunction "1_1") (pintype "passive"))
      (node (ref "U1") (pin "35") (pinfunction "PB14_35") (pintype "bidirectional"))
    )
    (net (code "29") (name "LED_BLUE") (class "Default")
      (node (ref "R15") (pin "1") (pinfunction "1_1") (pintype "passive"))
      (node (ref "U1") (pin "36") (pinfunction "PB15_36") (pintype "bidirectional"))
    )
    (net (code "30") (name "MAG_DRDY") (class "Default")
      (node (ref "U1") (pin "27") (pinfunction "PB1_27") (pintype "bidirectional"))
      (node (ref "U11") (pin "15") (pinfunction "DRDY_15") (pintype "bidirectional"))
    )
    (net (code "31") (name "MPU_CS") (class "Default")
      (node (ref "U1") (pin "26") (pinfunction "PB0_26") (pintype "bidirectional"))
      (node (ref "U14") (pin "8") (pinfunction "/CS_8") (pintype "bidirectional"))
    )
    (net (code "32") (name "Net-(D1-A)") (class "Default")
      (node (ref "D1") (pin "ANODE") (pinfunction "A_ANODE") (pintype "passive"))
      (node (ref "L8") (pin "1") (pinfunction "1_1") (pintype "passive"))
    )
    (net (code "33") (name "Net-(D2-CC)") (class "Default")
      (node (ref "D2") (pin "3") (pinfunction "CC_3") (pintype "passive"))
      (node (ref "J7") (pin "1") (pinfunction "S_1") (pintype "passive"))
      (node (ref "R22") (pin "2") (pinfunction "2_2") (pintype "passive"))
    )
    (net (code "34") (name "Net-(F1-Pad2)") (class "Default")
      (node (ref "F1") (pin "2") (pinfunction "2_2") (pintype "bidirectional"))
      (node (ref "L2") (pin "1") (pinfunction "1_1") (pintype "passive"))
    )
    (net (code "35") (name "Net-(F2-Pad1)") (class "Default")
      (node (ref "F2") (pin "1") (pinfunction "1_1") (pintype "bidirectional"))
      (node (ref "JP2") (pin "2") (pinfunction "2_2") (pintype "passive"))
    )
    (net (code "36") (name "Net-(F2-Pad2)") (class "Default")
      (node (ref "F2") (pin "2") (pinfunction "2_2") (pintype "bidirectional"))
      (node (ref "L3") (pin "1") (pinfunction "1_1") (pintype "passive"))
    )
    (net (code "37") (name "Net-(J1A-S)") (class "Default")
      (node (ref "J1") (pin "1") (pinfunction "S_1") (pintype "passive"))
      (node (ref "Q2") (pin "1") (pinfunction "D_1") (pintype "passive"))
      (node (ref "Q2") (pin "2") (pinfunction "D1_2") (pintype "passive"))
      (node (ref "Q2") (pin "5") (pinfunction "D2_5") (pintype "passive"))
      (node (ref "Q2") (pin "6") (pinfunction "D3_6") (pintype "passive"))
    )
    (net (code "38") (name "Net-(J1B-S)") (class "Default")
      (node (ref "J1") (pin "10") (pinfunction "S_10") (pintype "passive"))
      (node (ref "U2") (pin "1") (pinfunction "B2_1") (pintype "bidirectional"))
    )
    (net (code "39") (name "Net-(J1C-S)") (class "Default")
      (node (ref "J1") (pin "11") (pinfunction "S_11") (pintype "passive"))
      (node (ref "U2") (pin "8") (pinfunction "B1_8") (pintype "bidirectional"))
    )
    (net (code "40") (name "Net-(J1D-S)") (class "Default")
      (node (ref "J1") (pin "12") (pinfunction "S_12") (pintype "passive"))
      (node (ref "U3") (pin "8") (pinfunction "B1_8") (pintype "bidirectional"))
    )
    (net (code "41") (name "Net-(J1H-S)") (class "Default")
      (node (ref "J1") (pin "2") (pinfunction "S_2") (pintype "passive"))
      (node (ref "L2") (pin "2") (pinfunction "2_2") (pintype "passive"))
    )
    (net (code "42") (name "Net-(J1L-S)") (class "Default")
      (node (ref "J1") (pin "6") (pinfunction "S_6") (pintype "passive"))
      (node (ref "R10") (pin "2") (pinfunction "2_2") (pintype "passive"))
    )
    (net (code "43") (name "Net-(J1O-S)") (class "Default")
      (node (ref "J1") (pin "9") (pinfunction "S_9") (pintype "passive"))
      (node (ref "U3") (pin "1") (pinfunction "B2_1") (pintype "bidirectional"))
    )
    (net (code "44") (name "Net-(J2D-S)") (class "Default")
      (node (ref "J2") (pin "12") (pinfunction "S_12") (pintype "passive"))
      (node (ref "J3") (pin "12") (pinfunction "S_12") (pintype "passive"))
    )
    (net (code "45") (name "Net-(J4A-S)") (class "Default")
      (node (ref "J4") (pin "1") (pinfunction "S_1") (pintype "passive"))
      (node (ref "L3") (pin "2") (pinfunction "2_2") (pintype "passive"))
    )
    (net (code "46") (name "Net-(J4B-S)") (class "Default")
      (node (ref "J4") (pin "2") (pinfunction "S_2") (pintype "passive"))
      (node (ref "L5") (pin "2") (pinfunction "2_2") (pintype "passive"))
    )
    (net (code "47") (name "Net-(J4C-S)") (class "Default")
      (node (ref "J4") (pin "3") (pinfunction "S_3") (pintype "passive"))
      (node (ref "L4") (pin "2") (pinfunction "2_2") (pintype "passive"))
    )
    (net (code "48") (name "Net-(J5-2)") (class "Default")
      (node (ref "J5") (pin "D-") (pinfunction "2_D-") (pintype "bidirectional"))
      (node (ref "R6") (pin "1") (pinfunction "1_1") (pintype "passive"))
    )
    (net (code "49") (name "Net-(J5-3)") (class "Default")
      (node (ref "J5") (pin "D+") (pinfunction "3_D+") (pintype "bidirectional"))
      (node (ref "R8") (pin "1") (pinfunction "1_1") (pintype "passive"))
    )
    (net (code "50") (name "Net-(J7B-S)") (class "Default")
      (node (ref "J7") (pin "2") (pinfunction "S_2") (pintype "passive"))
      (node (ref "Q3") (pin "3") (pinfunction "D_3") (pintype "passive"))
      (node (ref "R22") (pin "1") (pinfunction "1_1") (pintype "passive"))
    )
    (net (code "51") (name "Net-(L10-Pad1)") (class "Default")
      (node (ref "L10") (pin "1") (pinfunction "1_1") (pintype "passive"))
      (node (ref "R11") (pin "2") (pinfunction "2_2") (pintype "passive"))
    )
    (net (code "52") (name "Net-(LED1-PadC)") (class "Default")
      (node (ref "LED1") (pin "C") (pinfunction "C_C") (pintype "passive"))
      (node (ref "R13") (pin "2") (pinfunction "2_2") (pintype "passive"))
    )
    (net (code "53") (name "Net-(LED2-PadC)") (class "Default")
      (node (ref "LED2") (pin "C") (pinfunction "C_C") (pintype "passive"))
      (node (ref "R14") (pin "2") (pinfunction "2_2") (pintype "passive"))
    )
    (net (code "54") (name "Net-(LED3-PadC)") (class "Default")
      (node (ref "LED3") (pin "C") (pinfunction "C_C") (pintype "passive"))
      (node (ref "R15") (pin "2") (pinfunction "2_2") (pintype "passive"))
    )
    (net (code "55") (name "Net-(Q2-S)") (class "Default")
      (node (ref "L1") (pin "2") (pinfunction "2_2") (pintype "passive"))
      (node (ref "Q2") (pin "4") (pinfunction "S_4") (pintype "passive"))
    )
    (net (code "56") (name "Net-(U1H-PH0{slash}OSC<=)") (class "Default")
      (node (ref "C3") (pin "1") (pinfunction "1_1") (pintype "passive"))
      (node (ref "U1") (pin "5") (pinfunction "PH0/OSC<=_5") (pintype "bidirectional"))
      (node (ref "X1") (pin "3") (pinfunction "3_3") (pintype "bidirectional"))
    )
    (net (code "57") (name "Net-(U1H-PH1{slash}OSC=>)") (class "Default")
      (node (ref "C4") (pin "2") (pinfunction "2_2") (pintype "passive"))
      (node (ref "U1") (pin "6") (pinfunction "PH1/OSC=>_6") (pintype "bidirectional"))
      (node (ref "X1") (pin "1") (pinfunction "1_1") (pintype "bidirectional"))
    )
    (net (code "58") (name "Net-(U1I-VCAP_1)") (class "Default")
      (node (ref "C11") (pin "1") (pinfunction "1_1") (pintype "passive"))
      (node (ref "U1") (pin "31") (pinfunction "VCAP_1_31") (pintype "power_in"))
    )
    (net (code "59") (name "Net-(U1I-VCAP_2)") (class "Default")
      (node (ref "C12") (pin "1") (pinfunction "1_1") (pintype "passive"))
      (node (ref "U1") (pin "47") (pinfunction "VCAP_2_47") (pintype "power_in"))
    )
    (net (code "60") (name "Net-(U1J-BOOT0)") (class "Default")
      (node (ref "BOOT0") (pin "P$1") (pinfunction "P$1_P$1") (pintype "passive"))
      (node (ref "R18") (pin "2") (pinfunction "2_2") (pintype "passive"))
      (node (ref "U1") (pin "60") (pinfunction "BOOT0_60") (pintype "input"))
    )
    (net (code "61") (name "Net-(U7-BP)") (class "Default")
      (node (ref "C16") (pin "1") (pinfunction "1_1") (pintype "passive"))
      (node (ref "U7") (pin "4") (pinfunction "BP_4") (pintype "input"))
    )
    (net (code "62") (name "Net-(U7-EN)") (class "Default")
      (node (ref "C14") (pin "1") (pinfunction "1_1") (pintype "passive"))
      (node (ref "L11") (pin "2") (pinfunction "2_2") (pintype "passive"))
      (node (ref "U7") (pin "1") (pinfunction "IN_1") (pintype "input"))
      (node (ref "U7") (pin "3") (pinfunction "EN_3") (pintype "input"))
    )
    (net (code "63") (name "Net-(U11-C1)") (class "Default")
      (node (ref "C23") (pin "1") (pinfunction "1_1") (pintype "passive"))
      (node (ref "U11") (pin "10") (pinfunction "C1_10") (pintype "bidirectional"))
    )
    (net (code "64") (name "Net-(U11-SETC)") (class "Default")
      (node (ref "C24") (pin "2") (pinfunction "2_2") (pintype "passive"))
      (node (ref "U11") (pin "12") (pinfunction "SETC_12") (pintype "bidirectional"))
    )
    (net (code "65") (name "Net-(U11-SETP)") (class "Default")
      (node (ref "C24") (pin "1") (pinfunction "1_1") (pintype "passive"))
      (node (ref "U11") (pin "8") (pinfunction "SETP_8") (pintype "bidirectional"))
    )
    (net (code "66") (name "Net-(U12-PLLFILT)") (class "Default")
      (node (ref "C25") (pin "1") (pinfunction "1_1") (pintype "passive"))
      (node (ref "U12") (pin "14") (pinfunction "PLLFILT_14") (pintype "bidirectional"))
    )
    (net (code "67") (name "Net-(U13-CLK)") (class "Default")
      (node (ref "RN1") (pin "8") (pinfunction "8_8") (pintype "passive"))
      (node (ref "U13") (pin "P$5") (pinfunction "CLK_P$5") (pintype "bidirectional"))
    )
    (net (code "68") (name "Net-(U13-CS)") (class "Default")
      (node (ref "RN1") (pin "5") (pinfunction "5_5") (pintype "passive"))
      (node (ref "U13") (pin "P$2") (pinfunction "CS_P$2") (pintype "bidirectional"))
    )
    (net (code "69") (name "Net-(U13-DI)") (class "Default")
      (node (ref "RN1") (pin "6") (pinfunction "6_6") (pintype "passive"))
      (node (ref "U13") (pin "P$3") (pinfunction "DI_P$3") (pintype "bidirectional"))
    )
    (net (code "70") (name "Net-(U13-DO)") (class "Default")
      (node (ref "RN1") (pin "7") (pinfunction "7_7") (pintype "passive"))
      (node (ref "U13") (pin "P$7") (pinfunction "DO_P$7") (pintype "bidirectional"))
    )
    (net (code "71") (name "Net-(U14-CPOUT)") (class "Default")
      (node (ref "C20") (pin "1") (pinfunction "1_1") (pintype "passive"))
      (node (ref "U14") (pin "20") (pinfunction "CPOUT_20") (pintype "bidirectional"))
    )
    (net (code "72") (name "Net-(U14-INT)") (class "Default")
      (node (ref "JP6") (pin "2") (pinfunction "2_2") (pintype "passive"))
      (node (ref "U14") (pin "12") (pinfunction "INT_12") (pintype "bidirectional"))
    )
    (net (code "73") (name "Net-(U14-REGOUT)") (class "Default")
      (node (ref "C26") (pin "1") (pinfunction "1_1") (pintype "passive"))
      (node (ref "U14") (pin "10") (pinfunction "REGOUT_10") (pintype "bidirectional"))
    )
    (net (code "74") (name "OTG_FS_DM") (class "Default")
      (node (ref "R6") (pin "2") (pinfunction "2_2") (pintype "passive"))
      (node (ref "U1") (pin "44") (pinfunction "PA11_44") (pintype "bidirectional"))
    )
    (net (code "75") (name "OTG_FS_DP") (class "Default")
      (node (ref "R8") (pin "2") (pinfunction "2_2") (pintype "passive"))
      (node (ref "U1") (pin "45") (pinfunction "PA12_45") (pintype "bidirectional"))
    )
    (net (code "76") (name "PB2-BOOT1") (class "Default")
      (node (ref "R5") (pin "1") (pinfunction "1_1") (pintype "passive"))
      (node (ref "U1") (pin "28") (pinfunction "PB2_28") (pintype "bidirectional"))
    )
    (net (code "77") (name "PPM_INPUT") (class "Default")
      (node (ref "J2") (pin "23") (pinfunction "S_23") (pintype "passive"))
      (node (ref "J3") (pin "23") (pinfunction "S_23") (pintype "passive"))
      (node (ref "R10") (pin "1") (pinfunction "1_1") (pintype "passive"))
      (node (ref "U1") (pin "43") (pinfunction "PA10_43") (pintype "bidirectional"))
    )
    (net (code "78") (name "RESET") (class "Default")
      (node (ref "!RESET") (pin "P$1") (pinfunction "P$1_P$1") (pintype "passive"))
      (node (ref "C17") (pin "2") (pinfunction "2_2") (pintype "passive"))
      (node (ref "R16") (pin "1") (pinfunction "1_1") (pintype "passive"))
      (node (ref "S1") (pin "A1") (pinfunction "1_A1") (pintype "passive"))
      (node (ref "U1") (pin "7") (pinfunction "NRST_7") (pintype "input"))
    )
    (net (code "79") (name "SPI1_MISO") (class "Default")
      (node (ref "SPI1_MISO") (pin "P$1") (pinfunction "P$1_P$1") (pintype "passive"))
      (node (ref "U1") (pin "22") (pinfunction "PA6_22") (pintype "bidirectional"))
      (node (ref "U12") (pin "4") (pinfunction "SDO/SA0_4") (pintype "bidirectional"))
      (node (ref "U14") (pin "9") (pinfunction "AD0/SDO_9") (pintype "bidirectional"))
      (node (ref "U15") (pin "1") (pinfunction "SDO_1") (pintype "bidirectional"))
    )
    (net (code "80") (name "SPI1_MOSI") (class "Default")
      (node (ref "SPI1_MOSI") (pin "P$1") (pinfunction "P$1_P$1") (pintype "passive"))
      (node (ref "U1") (pin "23") (pinfunction "PA7_23") (pintype "bidirectional"))
      (node (ref "U12") (pin "3") (pinfunction "SDA/SDI/SDO_3") (pintype "bidirectional"))
      (node (ref "U14") (pin "24") (pinfunction "SDA/SDI_24") (pintype "bidirectional"))
      (node (ref "U15") (pin "2") (pinfunction "SDI/SDA_2") (pintype "bidirectional"))
    )
    (net (code "81") (name "SPI1_SCK") (class "Default")
      (node (ref "SPI1_SCK") (pin "P$1") (pinfunction "P$1_P$1") (pintype "passive"))
      (node (ref "U1") (pin "21") (pinfunction "PA5_21") (pintype "bidirectional"))
      (node (ref "U12") (pin "2") (pinfunction "SCL/SPC_2") (pintype "input"))
      (node (ref "U14") (pin "23") (pinfunction "SCL/SCLK_23") (pintype "bidirectional"))
      (node (ref "U15") (pin "12") (pinfunction "SCK/SCL_12") (pintype "bidirectional"))
    )
    (net (code "82") (name "SPI3_MISO") (class "Default")
      (node (ref "R23") (pin "1") (pinfunction "1_1") (pintype "passive"))
      (node (ref "RN1") (pin "2") (pinfunction "2_2") (pintype "passive"))
      (node (ref "U1") (pin "52") (pinfunction "PC11_52") (pintype "bidirectional"))
    )
    (net (code "83") (name "SPI3_MOSI") (class "Default")
      (node (ref "RN1") (pin "3") (pinfunction "3_3") (pintype "passive"))
      (node (ref "U1") (pin "57") (pinfunction "PB5_57") (pintype "bidirectional"))
    )
    (net (code "84") (name "SPI3_NSS") (class "Default")
      (node (ref "RN1") (pin "4") (pinfunction "4_4") (pintype "passive"))
      (node (ref "U1") (pin "20") (pinfunction "PA4_20") (pintype "bidirectional"))
    )
    (net (code "85") (name "SPI3_SCK") (class "Default")
      (node (ref "RN1") (pin "1") (pinfunction "1_1") (pintype "passive"))
      (node (ref "U1") (pin "51") (pinfunction "PC10_51") (pintype "bidirectional"))
    )
    (net (code "86") (name "UART5_RX") (class "Default")
      (node (ref "J2") (pin "16") (pinfunction "S_16") (pintype "passive"))
      (node (ref "J3") (pin "16") (pinfunction "S_16") (pintype "passive"))
      (node (ref "U1") (pin "54") (pinfunction "PD2_54") (pintype "bidirectional"))
    )
    (net (code "87") (name "UART5_TX") (class "Default")
      (node (ref "J2") (pin "15") (pinfunction "S_15") (pintype "passive"))
      (node (ref "J3") (pin "15") (pinfunction "S_15") (pintype "passive"))
      (node (ref "U1") (pin "53") (pinfunction "PC12_53") (pintype "bidirectional"))
    )
    (net (code "88") (name "USART1_RX") (class "Default")
      (node (ref "U1") (pin "59") (pinfunction "PB7_59") (pintype "bidirectional"))
      (node (ref "U4") (pin "4") (pinfunction "A2_4") (pintype "bidirectional"))
    )
    (net (code "89") (name "USART1_RX_EXT") (class "Default")
      (node (ref "J1") (pin "7") (pinfunction "S_7") (pintype "passive"))
      (node (ref "J2") (pin "8") (pinfunction "S_8") (pintype "passive"))
      (node (ref "J3") (pin "8") (pinfunction "S_8") (pintype "passive"))
      (node (ref "U4") (pin "1") (pinfunction "B2_1") (pintype "bidirectional"))
    )
    (net (code "90") (name "USART1_TX") (class "Default")
      (node (ref "U1") (pin "58") (pinfunction "PB6_58") (pintype "bidirectional"))
      (node (ref "U4") (pin "5") (pinfunction "A1_5") (pintype "bidirectional"))
    )
    (net (code "91") (name "USART1_TX_EXT") (class "Default")
      (node (ref "J1") (pin "8") (pinfunction "S_8") (pintype "passive"))
      (node (ref "J2") (pin "7") (pinfunction "S_7") (pintype "passive"))
      (node (ref "J3") (pin "7") (pinfunction "S_7") (pintype "passive"))
      (node (ref "U4") (pin "8") (pinfunction "B1_8") (pintype "bidirectional"))
    )
    (net (code "92") (name "USART2_CTS") (class "Default")
      (node (ref "J2") (pin "19") (pinfunction "S_19") (pintype "passive"))
      (node (ref "J3") (pin "19") (pinfunction "S_19") (pintype "passive"))
      (node (ref "U1") (pin "14") (pinfunction "PA0_14") (pintype "bidirectional"))
      (node (ref "U2") (pin "5") (pinfunction "A1_5") (pintype "bidirectional"))
    )
    (net (code "93") (name "USART2_RTS") (class "Default")
      (node (ref "J2") (pin "20") (pinfunction "S_20") (pintype "passive"))
      (node (ref "J3") (pin "20") (pinfunction "S_20") (pintype "passive"))
      (node (ref "U1") (pin "15") (pinfunction "PA1_15") (pintype "bidirectional"))
      (node (ref "U2") (pin "4") (pinfunction "A2_4") (pintype "bidirectional"))
    )
    (net (code "94") (name "USART2_RX") (class "Default")
      (node (ref "J2") (pin "22") (pinfunction "S_22") (pintype "passive"))
      (node (ref "J3") (pin "22") (pinfunction "S_22") (pintype "passive"))
      (node (ref "U1") (pin "17") (pinfunction "PA3_17") (pintype "bidirectional"))
      (node (ref "U3") (pin "4") (pinfunction "A2_4") (pintype "bidirectional"))
    )
    (net (code "95") (name "USART2_TX") (class "Default")
      (node (ref "J2") (pin "21") (pinfunction "S_21") (pintype "passive"))
      (node (ref "J3") (pin "21") (pinfunction "S_21") (pintype "passive"))
      (node (ref "U1") (pin "16") (pinfunction "PA2_16") (pintype "bidirectional"))
      (node (ref "U3") (pin "5") (pinfunction "A1_5") (pintype "bidirectional"))
    )
    (net (code "96") (name "USART6_RX") (class "Default")
      (node (ref "J2") (pin "14") (pinfunction "S_14") (pintype "passive"))
      (node (ref "J3") (pin "14") (pinfunction "S_14") (pintype "passive"))
      (node (ref "L4") (pin "1") (pinfunction "1_1") (pintype "passive"))
      (node (ref "U1") (pin "38") (pinfunction "PC7_38") (pintype "bidirectional"))
      (node (ref "USART6_RX") (pin "P$1") (pinfunction "P$1_P$1") (pintype "passive"))
    )
    (net (code "97") (name "USART6_TX") (class "Default")
      (node (ref "J2") (pin "13") (pinfunction "S_13") (pintype "passive"))
      (node (ref "J3") (pin "13") (pinfunction "S_13") (pintype "passive"))
      (node (ref "L5") (pin "1") (pinfunction "1_1") (pintype "passive"))
      (node (ref "U1") (pin "37") (pinfunction "PC6_37") (pintype "bidirectional"))
      (node (ref "USART6_TX") (pin "P$1") (pinfunction "P$1_P$1") (pintype "passive"))
    )
    (net (code "98") (name "VBAT_IN") (class "Default")
      (node (ref "D2") (pin "1") (pinfunction "A1_1") (pintype "passive"))
      (node (ref "J1") (pin "5") (pinfunction "S_5") (pintype "passive"))
      (node (ref "L10") (pin "2") (pinfunction "2_2") (pintype "passive"))
    )
    (net (code "99") (name "VBUS") (class "Default")
      (node (ref "J5") (pin "VBUS") (pinfunction "1_VBUS") (pintype "power_in"))
      (node (ref "L8") (pin "2") (pinfunction "2_2") (pintype "passive"))
      (node (ref "U1") (pin "42") (pinfunction "PA9_42") (pintype "bidirectional"))
    )
    (net (code "100") (name "VDD_3V3") (class "Default")
      (node (ref "C10") (pin "1") (pinfunction "1_1") (pintype "passive"))
      (node (ref "C2") (pin "1") (pinfunction "1_1") (pintype "passive"))
      (node (ref "C6") (pin "A") (pinfunction "+_A") (pintype "passive"))
      (node (ref "C8") (pin "1") (pinfunction "1_1") (pintype "passive"))
      (node (ref "C9") (pin "1") (pinfunction "1_1") (pintype "passive"))
      (node (ref "F1") (pin "1") (pinfunction "1_1") (pintype "bidirectional"))
      (node (ref "J6") (pin "1") (pinfunction "S_1") (pintype "passive"))
      (node (ref "JP1") (pin "1") (pinfunction "1_1") (pintype "passive"))
      (node (ref "JP2") (pin "3") (pinfunction "3_3") (pintype "passive"))
      (node (ref "LED1") (pin "A") (pinfunction "A_A") (pintype "passive"))
      (node (ref "LED2") (pin "A") (pinfunction "A_A") (pintype "passive"))
      (node (ref "LED3") (pin "A") (pinfunction "A_A") (pintype "passive"))
      (node (ref "R16") (pin "2") (pinfunction "2_2") (pintype "passive"))
      (node (ref "R19") (pin "2") (pinfunction "2_2") (pintype "passive"))
      (node (ref "R20") (pin "2") (pinfunction "2_2") (pintype "passive"))
      (node (ref "R23") (pin "2") (pinfunction "2_2") (pintype "passive"))
      (node (ref "R7") (pin "2") (pinfunction "2_2") (pintype "passive"))
      (node (ref "R9") (pin "2") (pinfunction "2_2") (pintype "passive"))
      (node (ref "U1") (pin "1") (pinfunction "VBAT_1") (pintype "power_in"))
      (node (ref "U1") (pin "19") (pinfunction "VDD_4_19") (pintype "power_in"))
      (node (ref "U1") (pin "32") (pinfunction "VDD_1_32") (pintype "power_in"))
      (node (ref "U1") (pin "48") (pinfunction "VDD_2_48") (pintype "power_in"))
      (node (ref "U1") (pin "64") (pinfunction "VDD_3_64") (pintype "power_in"))
      (node (ref "U12") (pin "1") (pinfunction "VDD_IO_1") (pintype "bidirectional"))
      (node (ref "U13") (pin "P$4") (pinfunction "VCC_P$4") (pintype "passive"))
      (node (ref "U15") (pin "3") (pinfunction "VDDIO_3") (pintype "bidirectional"))
      (node (ref "U2") (pin "3") (pinfunction "VCCA_3") (pintype "input"))
      (node (ref "U2") (pin "6") (pinfunction "OE_6") (pintype "input"))
      (node (ref "U3") (pin "3") (pinfunction "VCCA_3") (pintype "input"))
      (node (ref "U3") (pin "6") (pinfunction "OE_6") (pintype "input"))
      (node (ref "U4") (pin "3") (pinfunction "VCCA_3") (pintype "input"))
      (node (ref "U4") (pin "6") (pinfunction "OE_6") (pintype "input"))
      (node (ref "U4") (pin "7") (pinfunction "VCCB_7") (pintype "input"))
      (node (ref "U5") (pin "1") (pinfunction "VCCA_1") (pintype "passive"))
      (node (ref "U6") (pin "2") (pinfunction "VOUT_2") (pintype "bidirectional"))
      (node (ref "U6") (pin "4") (pinfunction "VOUT-TAB_4") (pintype "bidirectional"))
      (node (ref "U8") (pin "8") (pinfunction "VCC_8") (pintype "power_in"))
      (node (ref "VDD_3V3") (pin "P$1") (pinfunction "P$1_P$1") (pintype "passive"))
    )
    (net (code "101") (name "VDD_3V3_ANALOG") (class "Default")
      (node (ref "C13") (pin "A") (pinfunction "+_A") (pintype "passive"))
      (node (ref "C15") (pin "1") (pinfunction "1_1") (pintype "passive"))
      (node (ref "C18") (pin "1") (pinfunction "1_1") (pintype "passive"))
      (node (ref "C19") (pin "1") (pinfunction "1_1") (pintype "passive"))
      (node (ref "C21") (pin "1") (pinfunction "1_1") (pintype "passive"))
      (node (ref "C22") (pin "1") (pinfunction "1_1") (pintype "passive"))
      (node (ref "C28") (pin "1") (pinfunction "1_1") (pintype "passive"))
      (node (ref "U1") (pin "13") (pinfunction "VDDA_13") (pintype "power_in"))
      (node (ref "U10") (pin "1") (pinfunction "VDD_1") (pintype "bidirectional"))
      (node (ref "U10") (pin "2") (pinfunction "PS_2") (pintype "bidirectional"))
      (node (ref "U10") (pin "4") (pinfunction "CSB1_4") (pintype "bidirectional"))
      (node (ref "U10") (pin "5") (pinfunction "CSB2_5") (pintype "bidirectional"))
      (node (ref "U11") (pin "13") (pinfunction "VDDIO_13") (pintype "bidirectional"))
      (node (ref "U11") (pin "2") (pinfunction "VDD_2") (pintype "bidirectional"))
      (node (ref "U11") (pin "4") (pinfunction "S1_VDDIO_4") (pintype "bidirectional"))
      (node (ref "U12") (pin "15") (pinfunction "RES_P15_VDD_15") (pintype "bidirectional"))
      (node (ref "U12") (pin "16") (pinfunction "VDD_16") (pintype "bidirectional"))
      (node (ref "U14") (pin "13") (pinfunction "VDD_13") (pintype "bidirectional"))
      (node (ref "U15") (pin "7") (pinfunction "VDD_7") (pintype "bidirectional"))
      (node (ref "U7") (pin "5") (pinfunction "OUT_5") (pintype "passive"))
      (node (ref "VDDA_3V3") (pin "P$1") (pinfunction "P$1_P$1") (pintype "passive"))
    )
    (net (code "102") (name "VDD_5V") (class "Default")
      (node (ref "C27") (pin "A") (pinfunction "+_A") (pintype "passive"))
      (node (ref "C7") (pin "1") (pinfunction "1_1") (pintype "passive"))
      (node (ref "D2") (pin "2") (pinfunction "A2_2") (pintype "passive"))
      (node (ref "JP1") (pin "3") (pinfunction "3_3") (pintype "passive"))
      (node (ref "JP2") (pin "1") (pinfunction "1_1") (pintype "passive"))
      (node (ref "L1") (pin "1") (pinfunction "1_1") (pintype "passive"))
      (node (ref "L11") (pin "1") (pinfunction "1_1") (pintype "passive"))
      (node (ref "Q1") (pin "4") (pinfunction "S_4") (pintype "passive"))
      (node (ref "R1") (pin "2") (pinfunction "2_2") (pintype "passive"))
      (node (ref "R2") (pin "2") (pinfunction "2_2") (pintype "passive"))
      (node (ref "U6") (pin "3") (pinfunction "VIN_3") (pintype "bidirectional"))
    )
    (net (code "103") (name "VDD_5V_IN") (class "Default")
      (node (ref "D1") (pin "CATHODE") (pinfunction "C_CATHODE") (pintype "passive"))
      (node (ref "J2") (pin "1") (pinfunction "S_1") (pintype "passive"))
      (node (ref "J2") (pin "2") (pinfunction "S_2") (pintype "passive"))
      (node (ref "J3") (pin "1") (pinfunction "S_1") (pintype "passive"))
      (node (ref "J3") (pin "2") (pinfunction "S_2") (pintype "passive"))
      (node (ref "Q1") (pin "1") (pinfunction "D_1") (pintype "passive"))
      (node (ref "Q1") (pin "2") (pinfunction "D1_2") (pintype "passive"))
      (node (ref "Q1") (pin "5") (pinfunction "D2_5") (pintype "passive"))
      (node (ref "Q1") (pin "6") (pinfunction "D3_6") (pintype "passive"))
    )
    (net (code "104") (name "VDD_IO") (class "Default")
      (node (ref "C1") (pin "1") (pinfunction "1_1") (pintype "passive"))
      (node (ref "JP1") (pin "2") (pinfunction "2_2") (pintype "passive"))
      (node (ref "U2") (pin "7") (pinfunction "VCCB_7") (pintype "input"))
      (node (ref "U3") (pin "7") (pinfunction "VCCB_7") (pintype "input"))
      (node (ref "U5") (pin "8") (pinfunction "VCCB_8") (pintype "passive"))
    )
    (net (code "105") (name "unconnected-(J4D-S-Pad4)") (class "Default")
      (node (ref "J4") (pin "4") (pinfunction "S_4") (pintype "passive"))
    )
    (net (code "106") (name "unconnected-(J5-4-PadID)") (class "Default")
      (node (ref "J5") (pin "ID") (pinfunction "4_ID") (pintype "passive"))
    )
    (net (code "107") (name "unconnected-(U8-WP-Pad7)") (class "Default")
      (node (ref "U8") (pin "7") (pinfunction "WP_7") (pintype "bidirectional"))
    )
    (net (code "108") (name "unconnected-(U10-SDO-Pad6)") (class "Default")
      (node (ref "U10") (pin "6") (pinfunction "SDO_6") (pintype "bidirectional"))
    )
    (net (code "109") (name "unconnected-(U11-NC_P3-Pad3)") (class "Default")
      (node (ref "U11") (pin "3") (pinfunction "NC_P3_3") (pintype "no_connect"))
    )
    (net (code "110") (name "unconnected-(U11-NC_P5-Pad5)") (class "Default")
      (node (ref "U11") (pin "5") (pinfunction "NC_P5_5") (pintype "no_connect"))
    )
    (net (code "111") (name "unconnected-(U11-NC_P6-Pad6)") (class "Default")
      (node (ref "U11") (pin "6") (pinfunction "NC_P6_6") (pintype "no_connect"))
    )
    (net (code "112") (name "unconnected-(U11-NC_P7-Pad7)") (class "Default")
      (node (ref "U11") (pin "7") (pinfunction "NC_P7_7") (pintype "no_connect"))
    )
    (net (code "113") (name "unconnected-(U11-NC_P14-Pad14)") (class "Default")
      (node (ref "U11") (pin "14") (pinfunction "NC_P14_14") (pintype "no_connect"))
    )
    (net (code "114") (name "unconnected-(U12-DRDY{slash}INT2-Pad6)") (class "Default")
      (node (ref "U12") (pin "6") (pinfunction "DRDY/INT2_6") (pintype "output"))
    )
    (net (code "115") (name "unconnected-(U12-INT1-Pad7)") (class "Default")
      (node (ref "U12") (pin "7") (pinfunction "INT1_7") (pintype "output"))
    )
    (net (code "116") (name "unconnected-(U14-AUX_CL-Pad7)") (class "Default")
      (node (ref "U14") (pin "7") (pinfunction "AUX_CL_7") (pintype "bidirectional"))
    )
    (net (code "117") (name "unconnected-(U14-AUX_DA-Pad6)") (class "Default")
      (node (ref "U14") (pin "6") (pinfunction "AUX_DA_6") (pintype "bidirectional"))
    )
    (net (code "118") (name "unconnected-(U14-CLKOUT-Pad22)") (class "Default")
      (node (ref "U14") (pin "22") (pinfunction "CLKOUT_22") (pintype "bidirectional"))
    )
    (net (code "119") (name "unconnected-(U14-NC1-Pad2)") (class "Default")
      (node (ref "U14") (pin "2") (pinfunction "NC1_2") (pintype "bidirectional"))
    )
    (net (code "120") (name "unconnected-(U14-NC2-Pad3)") (class "Default")
      (node (ref "U14") (pin "3") (pinfunction "NC2_3") (pintype "bidirectional"))
    )
    (net (code "121") (name "unconnected-(U14-NC3-Pad4)") (class "Default")
      (node (ref "U14") (pin "4") (pinfunction "NC3_4") (pintype "bidirectional"))
    )
    (net (code "122") (name "unconnected-(U14-NC4-Pad5)") (class "Default")
      (node (ref "U14") (pin "5") (pinfunction "NC4_5") (pintype "bidirectional"))
    )
    (net (code "123") (name "unconnected-(U14-NC5-Pad14)") (class "Default")
      (node (ref "U14") (pin "14") (pinfunction "NC5_14") (pintype "bidirectional"))
    )
    (net (code "124") (name "unconnected-(U14-NC6-Pad15)") (class "Default")
      (node (ref "U14") (pin "15") (pinfunction "NC6_15") (pintype "bidirectional"))
    )
    (net (code "125") (name "unconnected-(U14-NC7-Pad16)") (class "Default")
      (node (ref "U14") (pin "16") (pinfunction "NC7_16") (pintype "bidirectional"))
    )
    (net (code "126") (name "unconnected-(U14-NC8-Pad17)") (class "Default")
      (node (ref "U14") (pin "17") (pinfunction "NC8_17") (pintype "bidirectional"))
    )
    (net (code "127") (name "unconnected-(U14-RESV1-Pad19)") (class "Default")
      (node (ref "U14") (pin "19") (pinfunction "RESV1_19") (pintype "bidirectional"))
    )
    (net (code "128") (name "unconnected-(U14-RESV2-Pad21)") (class "Default")
      (node (ref "U14") (pin "21") (pinfunction "RESV2_21") (pintype "bidirectional"))
    )
    (net (code "129") (name "unconnected-(U15-INT1-Pad5)") (class "Default")
      (node (ref "U15") (pin "5") (pinfunction "INT1_5") (pintype "bidirectional"))
    )
    (net (code "130") (name "unconnected-(U15-INT2-Pad6)") (class "Default")
      (node (ref "U15") (pin "6") (pinfunction "INT2_6") (pintype "bidirectional"))
    )
    (net (code "131") (name "~{JTRST}") (class "Default")
      (node (ref "!JTRST") (pin "P$1") (pinfunction "P$1_P$1") (pintype "passive"))
      (node (ref "J6") (pin "10") (pinfunction "S_10") (pintype "passive"))
      (node (ref "U1") (pin "56") (pinfunction "PB4_56") (pintype "bidirectional"))
    )
  )
)
